# MotherForSmoothie_preliminary.net
KiCad netlist of a schematic drawn in EAGLE
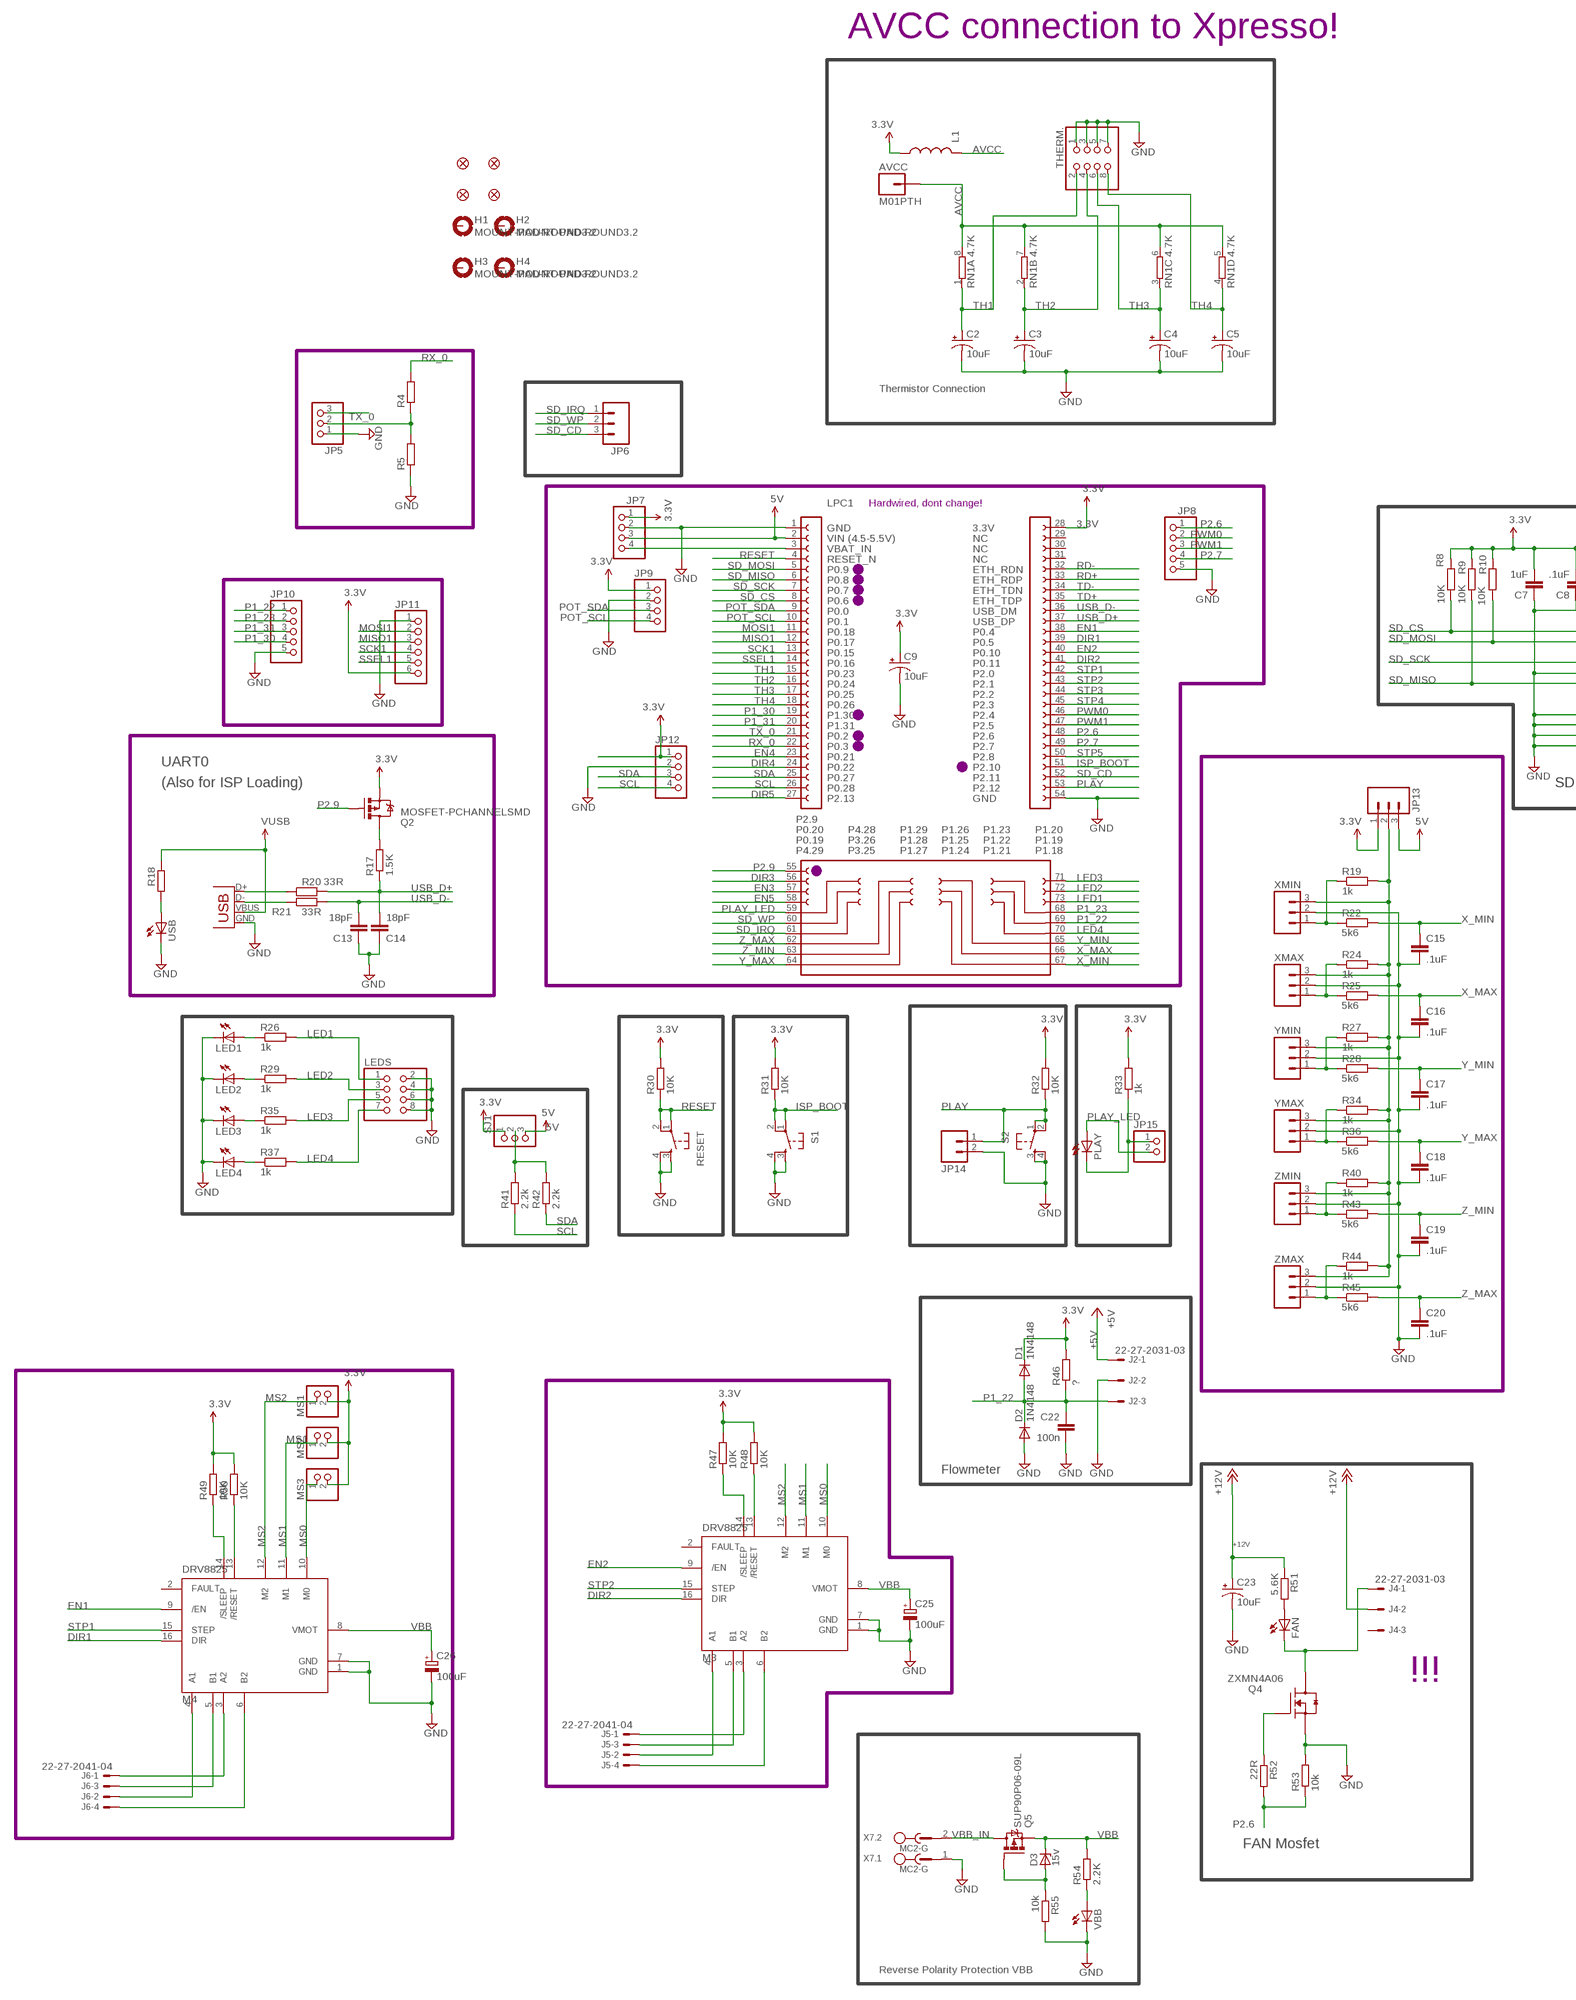
[diagram p0: schematic, sheet 1, part 1 of 2]
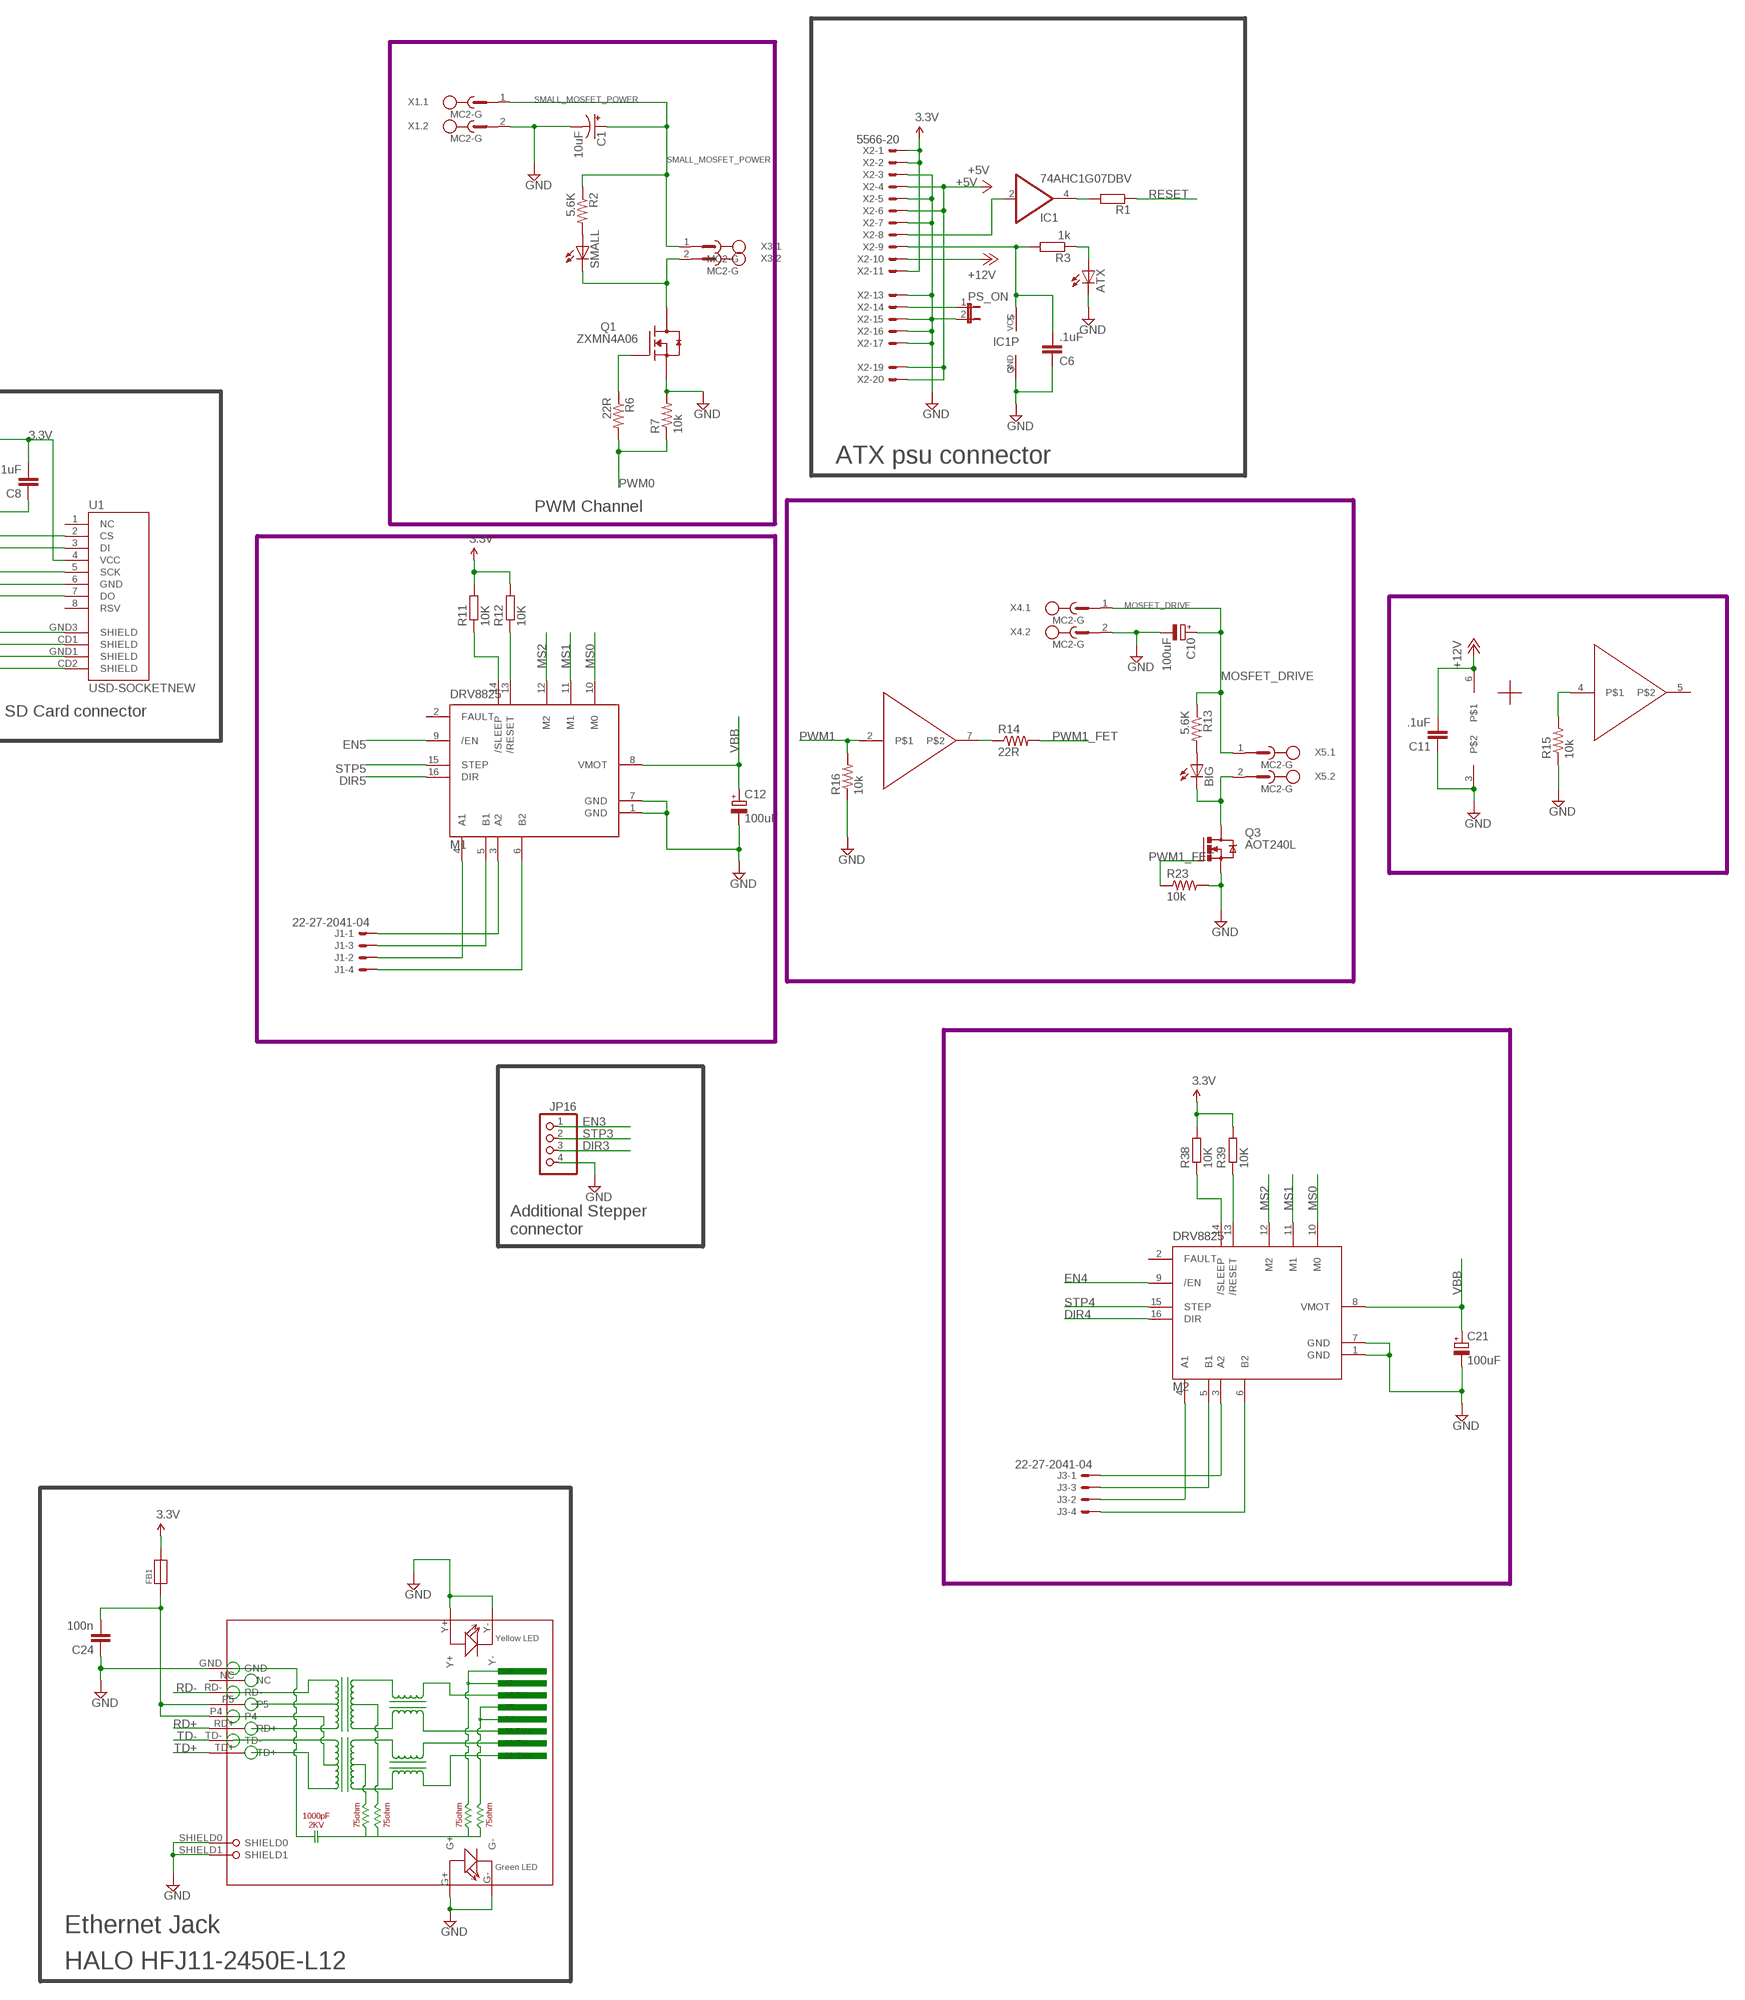
[diagram p1: schematic, sheet 1, part 2 of 2]

(export (version "E")
  (design (tool "Eeschema 10.0.6"))
  (components
    (comp (ref "ATX")
      (value "LEDCHIPLED_0805")
      (footprint "eagle-import:CHIPLED_0805")
      (libsource (lib "eagle-import") (part "LEDCHIPLED_0805"))
    )
    (comp (ref "AVCC")
      (value "M01PTH")
      (footprint "eagle-import:1X01")
      (libsource (lib "eagle-import") (part "M01PTH"))
    )
    (comp (ref "BIG")
      (value "LEDCHIP-LED0805")
      (footprint "eagle-import:CHIP-LED0805")
      (libsource (lib "eagle-import") (part "LEDCHIP-LED0805"))
    )
    (comp (ref "C1")
      (value "10uF")
      (footprint "eagle-import:EIA3216")
      (libsource (lib "eagle-import") (part "CAP_POL1206"))
    )
    (comp (ref "C2")
      (value "10uF")
      (footprint "eagle-import:EIA3216")
      (libsource (lib "eagle-import") (part "CAP_POL1206"))
    )
    (comp (ref "C3")
      (value "10uF")
      (footprint "eagle-import:EIA3216")
      (libsource (lib "eagle-import") (part "CAP_POL1206"))
    )
    (comp (ref "C4")
      (value "10uF")
      (footprint "eagle-import:EIA3216")
      (libsource (lib "eagle-import") (part "CAP_POL1206"))
    )
    (comp (ref "C5")
      (value "10uF")
      (footprint "eagle-import:EIA3216")
      (libsource (lib "eagle-import") (part "CAP_POL1206"))
    )
    (comp (ref "C6")
      (value ".1uF")
      (footprint "eagle-import:C0603")
      (libsource (lib "eagle-import") (part "C-EUC0603"))
    )
    (comp (ref "C7")
      (value "1uF")
      (footprint "eagle-import:C0603")
      (libsource (lib "eagle-import") (part "C-EUC0603"))
    )
    (comp (ref "C8")
      (value ".1uF")
      (footprint "eagle-import:C0603")
      (libsource (lib "eagle-import") (part "C-EUC0603"))
    )
    (comp (ref "C9")
      (value "10uF")
      (footprint "eagle-import:EIA3216")
      (libsource (lib "eagle-import") (part "CAP_POL1206"))
    )
    (comp (ref "C10")
      (value "100uF")
      (footprint "eagle-import:E5-8,5")
      (libsource (lib "eagle-import") (part "CPOL-EUE5-8.5"))
    )
    (comp (ref "C11")
      (value ".1uF")
      (footprint "eagle-import:C0603")
      (libsource (lib "eagle-import") (part "C-EUC0603"))
    )
    (comp (ref "C12")
      (value "100uF")
      (footprint "eagle-import:E5-8,5")
      (libsource (lib "eagle-import") (part "CPOL-EUE5-8.5"))
    )
    (comp (ref "C13")
      (value "18pF")
      (footprint "eagle-import:C0603")
      (libsource (lib "eagle-import") (part "C-EUC0603"))
    )
    (comp (ref "C14")
      (value "18pF")
      (footprint "eagle-import:C0603")
      (libsource (lib "eagle-import") (part "C-EUC0603"))
    )
    (comp (ref "C15")
      (value ".1uF")
      (footprint "eagle-import:C0603")
      (libsource (lib "eagle-import") (part "C-EUC0603"))
    )
    (comp (ref "C16")
      (value ".1uF")
      (footprint "eagle-import:C0603")
      (libsource (lib "eagle-import") (part "C-EUC0603"))
    )
    (comp (ref "C17")
      (value ".1uF")
      (footprint "eagle-import:C0603")
      (libsource (lib "eagle-import") (part "C-EUC0603"))
    )
    (comp (ref "C18")
      (value ".1uF")
      (footprint "eagle-import:C0603")
      (libsource (lib "eagle-import") (part "C-EUC0603"))
    )
    (comp (ref "C19")
      (value ".1uF")
      (footprint "eagle-import:C0603")
      (libsource (lib "eagle-import") (part "C-EUC0603"))
    )
    (comp (ref "C20")
      (value ".1uF")
      (footprint "eagle-import:C0603")
      (libsource (lib "eagle-import") (part "C-EUC0603"))
    )
    (comp (ref "C21")
      (value "100uF")
      (footprint "eagle-import:E5-8,5")
      (libsource (lib "eagle-import") (part "CPOL-EUE5-8.5"))
    )
    (comp (ref "C22")
      (value "100n")
      (footprint "eagle-import:C0603")
      (libsource (lib "eagle-import") (part "C-EUC0603"))
    )
    (comp (ref "C23")
      (value "10uF")
      (footprint "eagle-import:EIA3216")
      (libsource (lib "eagle-import") (part "CAP_POL1206"))
    )
    (comp (ref "C24")
      (value "100n")
      (footprint "eagle-import:C0603")
      (libsource (lib "eagle-import") (part "C-EUC0603"))
    )
    (comp (ref "C25")
      (value "100uF")
      (footprint "eagle-import:E5-8,5")
      (libsource (lib "eagle-import") (part "CPOL-EUE5-8.5"))
    )
    (comp (ref "C26")
      (value "100uF")
      (footprint "eagle-import:E5-8,5")
      (libsource (lib "eagle-import") (part "CPOL-EUE5-8.5"))
    )
    (comp (ref "D1")
      (value "1N4148")
      (footprint "eagle-import:MINIMELF")
      (libsource (lib "eagle-import") (part "DIODE-MINIMELF"))
    )
    (comp (ref "D2")
      (value "1N4148")
      (footprint "eagle-import:MINIMELF")
      (libsource (lib "eagle-import") (part "DIODE-MINIMELF"))
    )
    (comp (ref "D3")
      (value "15v")
      (footprint "eagle-import:SMB")
      (libsource (lib "eagle-import") (part "ZENER-DIODESMB"))
    )
    (comp (ref "FAN")
      (value "LEDCHIPLED_0805")
      (footprint "eagle-import:CHIPLED_0805")
      (libsource (lib "eagle-import") (part "LEDCHIPLED_0805"))
    )
    (comp (ref "FB1")
      (value "FERRITE")
      (footprint "eagle-import:0603")
      (libsource (lib "eagle-import") (part "FERRITE"))
    )
    (comp (ref "H1")
      (value "MOUNT-PAD-ROUND3.2")
      (footprint "eagle-import:3,2-PAD")
      (libsource (lib "eagle-import") (part "MOUNT-PAD-ROUND3.2"))
    )
    (comp (ref "H2")
      (value "MOUNT-PAD-ROUND3.2")
      (footprint "eagle-import:3,2-PAD")
      (libsource (lib "eagle-import") (part "MOUNT-PAD-ROUND3.2"))
    )
    (comp (ref "H3")
      (value "MOUNT-PAD-ROUND3.2")
      (footprint "eagle-import:3,2-PAD")
      (libsource (lib "eagle-import") (part "MOUNT-PAD-ROUND3.2"))
    )
    (comp (ref "H4")
      (value "MOUNT-PAD-ROUND3.2")
      (footprint "eagle-import:3,2-PAD")
      (libsource (lib "eagle-import") (part "MOUNT-PAD-ROUND3.2"))
    )
    (comp (ref "IC1")
      (value "74AHC1G07DBV")
      (footprint "eagle-import:SOT23-5")
      (libsource (lib "eagle-import") (part "741G07DBVAHC"))
    )
    (comp (ref "IC2")
      (value "TC4427")
      (footprint "eagle-import:SOIC8")
      (libsource (lib "eagle-import") (part "TC4427"))
    )
    (comp (ref "J1")
      (value "22-27-2041-04")
      (footprint "eagle-import:6410-04")
      (libsource (lib "eagle-import") (part "22-?-0427-2041"))
    )
    (comp (ref "J2")
      (value "22-27-2031-03")
      (footprint "eagle-import:6410-03")
      (libsource (lib "eagle-import") (part "22-?-0327-2031"))
    )
    (comp (ref "J3")
      (value "22-27-2041-04")
      (footprint "eagle-import:6410-04")
      (libsource (lib "eagle-import") (part "22-?-0427-2041"))
    )
    (comp (ref "J4")
      (value "22-27-2031-03")
      (footprint "eagle-import:6410-03")
      (libsource (lib "eagle-import") (part "22-?-0327-2031"))
    )
    (comp (ref "J5")
      (value "22-27-2041-04")
      (footprint "eagle-import:6410-04")
      (libsource (lib "eagle-import") (part "22-?-0427-2041"))
    )
    (comp (ref "J6")
      (value "22-27-2041-04")
      (footprint "eagle-import:6410-04")
      (libsource (lib "eagle-import") (part "22-?-0427-2041"))
    )
    (comp (ref "JP1")
      (value "FIDUCIAL1X2")
      (footprint "eagle-import:FIDUCIAL-1X2")
      (libsource (lib "eagle-import") (part "FIDUCIAL1X2"))
    )
    (comp (ref "JP2")
      (value "FIDUCIAL1X2")
      (footprint "eagle-import:FIDUCIAL-1X2")
      (libsource (lib "eagle-import") (part "FIDUCIAL1X2"))
    )
    (comp (ref "JP3")
      (value "FIDUCIAL1X2")
      (footprint "eagle-import:FIDUCIAL-1X2")
      (libsource (lib "eagle-import") (part "FIDUCIAL1X2"))
    )
    (comp (ref "JP4")
      (value "FIDUCIAL1X2")
      (footprint "eagle-import:FIDUCIAL-1X2")
      (libsource (lib "eagle-import") (part "FIDUCIAL1X2"))
    )
    (comp (ref "JP5")
      (value "PINHD-1X3_2.54-SMD")
      (footprint "eagle-import:1X03SMD")
      (libsource (lib "eagle-import") (part "PINHD-1X3_2.54-SMD"))
    )
    (comp (ref "JP6")
      (value "M031X03_NO_SILK")
      (footprint "eagle-import:1X03_NO_SILK")
      (libsource (lib "eagle-import") (part "M031X03_NO_SILK"))
    )
    (comp (ref "JP7")
      (value "PINHD-1X4_2.54-SMD")
      (footprint "eagle-import:1X04SMD")
      (libsource (lib "eagle-import") (part "PINHD-1X4_2.54-SMD"))
    )
    (comp (ref "JP8")
      (value "PINHD-1X5_2.54-SMD")
      (footprint "eagle-import:1X05SMD")
      (libsource (lib "eagle-import") (part "PINHD-1X5_2.54-SMD"))
    )
    (comp (ref "JP9")
      (value "PINHD-1X4_2.54-SMD")
      (footprint "eagle-import:1X04SMD")
      (libsource (lib "eagle-import") (part "PINHD-1X4_2.54-SMD"))
    )
    (comp (ref "JP10")
      (value "PINHD-1X5_2.54-SMD")
      (footprint "eagle-import:1X05SMD")
      (libsource (lib "eagle-import") (part "PINHD-1X5_2.54-SMD"))
    )
    (comp (ref "JP11")
      (value "PINHD-1X6_2.54-SMD")
      (footprint "eagle-import:1X06SMD")
      (libsource (lib "eagle-import") (part "PINHD-1X6_2.54-SMD"))
    )
    (comp (ref "JP12")
      (value "PINHD-1X4_2.54-SMD")
      (footprint "eagle-import:1X04SMD")
      (libsource (lib "eagle-import") (part "PINHD-1X4_2.54-SMD"))
    )
    (comp (ref "JP13")
      (value "M031X03_NO_SILK")
      (footprint "eagle-import:1X03_NO_SILK")
      (libsource (lib "eagle-import") (part "M031X03_NO_SILK"))
    )
    (comp (ref "JP14")
      (value "M02PTH")
      (footprint "eagle-import:1X02")
      (libsource (lib "eagle-import") (part "M02PTH"))
    )
    (comp (ref "JP15")
      (value "PINHD-1X2_2.54-SMD")
      (footprint "eagle-import:1X02SMD")
      (libsource (lib "eagle-import") (part "PINHD-1X2_2.54-SMD"))
    )
    (comp (ref "JP16")
      (value "PINHD-1X4_2.54-SMD")
      (footprint "eagle-import:1X04SMD")
      (libsource (lib "eagle-import") (part "PINHD-1X4_2.54-SMD"))
    )
    (comp (ref "L1")
      (value "INDUCTOR0603")
      (footprint "eagle-import:0603")
      (libsource (lib "eagle-import") (part "INDUCTOR0603"))
    )
    (comp (ref "LED1")
      (value "LEDCHIP-LED0805")
      (footprint "eagle-import:CHIP-LED0805")
      (libsource (lib "eagle-import") (part "LEDCHIP-LED0805"))
    )
    (comp (ref "LED2")
      (value "LEDCHIP-LED0805")
      (footprint "eagle-import:CHIP-LED0805")
      (libsource (lib "eagle-import") (part "LEDCHIP-LED0805"))
    )
    (comp (ref "LED3")
      (value "LEDCHIP-LED0805")
      (footprint "eagle-import:CHIP-LED0805")
      (libsource (lib "eagle-import") (part "LEDCHIP-LED0805"))
    )
    (comp (ref "LED4")
      (value "LEDCHIP-LED0805")
      (footprint "eagle-import:CHIP-LED0805")
      (libsource (lib "eagle-import") (part "LEDCHIP-LED0805"))
    )
    (comp (ref "LEDS")
      (value "PINHD-2X4_2.54-SMD")
      (footprint "eagle-import:2X04SMD")
      (libsource (lib "eagle-import") (part "PINHD-2X4_2.54-SMD"))
    )
    (comp (ref "LPC1")
      (value "LPCXPRESSO_LPC1769SMD_PART")
      (footprint "eagle-import:LPCXPRESSO_LPC1769_SMD")
      (libsource (lib "eagle-import") (part "LPCXPRESSO_LPC1769SMD_PART"))
    )
    (comp (ref "M1")
      (value "DRV8825")
      (footprint "eagle-import:DRV8825")
      (libsource (lib "eagle-import") (part "DRV8825"))
    )
    (comp (ref "M2")
      (value "DRV8825")
      (footprint "eagle-import:DRV8825")
      (libsource (lib "eagle-import") (part "DRV8825"))
    )
    (comp (ref "M3")
      (value "DRV8825")
      (footprint "eagle-import:DRV8825")
      (libsource (lib "eagle-import") (part "DRV8825"))
    )
    (comp (ref "M4")
      (value "DRV8825")
      (footprint "eagle-import:DRV8825")
      (libsource (lib "eagle-import") (part "DRV8825"))
    )
    (comp (ref "MS1")
      (value "PINHD-1X2_2.54-SMD")
      (footprint "eagle-import:1X02SMD")
      (libsource (lib "eagle-import") (part "PINHD-1X2_2.54-SMD"))
    )
    (comp (ref "MS2")
      (value "PINHD-1X2_2.54-SMD")
      (footprint "eagle-import:1X02SMD")
      (libsource (lib "eagle-import") (part "PINHD-1X2_2.54-SMD"))
    )
    (comp (ref "MS3")
      (value "PINHD-1X2_2.54-SMD")
      (footprint "eagle-import:1X02SMD")
      (libsource (lib "eagle-import") (part "PINHD-1X2_2.54-SMD"))
    )
    (comp (ref "PLAY")
      (value "LEDCHIPLED_0805")
      (footprint "eagle-import:CHIPLED_0805")
      (libsource (lib "eagle-import") (part "LEDCHIPLED_0805"))
    )
    (comp (ref "PS_ON")
      (value "JP1E")
      (footprint "eagle-import:JP1")
      (libsource (lib "eagle-import") (part "JP1E"))
    )
    (comp (ref "Q1")
      (value "ZXMN4A06")
      (footprint "eagle-import:SOT230P700X160-4N")
      (libsource (lib "eagle-import") (part "MOSFET-NCH_SOT-223"))
    )
    (comp (ref "Q2")
      (value "MOSFET-PCHANNELSMD")
      (footprint "eagle-import:SOT23-3")
      (libsource (lib "eagle-import") (part "MOSFET-PCHANNELSMD"))
    )
    (comp (ref "Q3")
      (value "AOT240L")
      (footprint "eagle-import:TO220BV")
      (libsource (lib "eagle-import") (part "IRF540"))
    )
    (comp (ref "Q4")
      (value "ZXMN4A06")
      (footprint "eagle-import:SOT230P700X160-4N")
      (libsource (lib "eagle-import") (part "MOSFET-NCH_SOT-223"))
    )
    (comp (ref "Q5")
      (value "SUP90P06-09L")
      (footprint "eagle-import:TO220BV")
      (libsource (lib "eagle-import") (part "IRF9530"))
    )
    (comp (ref "R1")
      (value "R-EU_R0603")
      (footprint "eagle-import:R0603")
      (libsource (lib "eagle-import") (part "R-EU_R0603"))
    )
    (comp (ref "R2")
      (value "5.6K")
      (footprint "eagle-import:R0603")
      (libsource (lib "eagle-import") (part "R-US_R0603"))
    )
    (comp (ref "R3")
      (value "1k")
      (footprint "eagle-import:R0603")
      (libsource (lib "eagle-import") (part "R-EU_R0603"))
    )
    (comp (ref "R4")
      (value "R-EU_R0603")
      (footprint "eagle-import:R0603")
      (libsource (lib "eagle-import") (part "R-EU_R0603"))
    )
    (comp (ref "R5")
      (value "R-EU_R0603")
      (footprint "eagle-import:R0603")
      (libsource (lib "eagle-import") (part "R-EU_R0603"))
    )
    (comp (ref "R6")
      (value "22R")
      (footprint "eagle-import:R0603")
      (libsource (lib "eagle-import") (part "R-US_R0603"))
    )
    (comp (ref "R7")
      (value "10k")
      (footprint "eagle-import:R0603")
      (libsource (lib "eagle-import") (part "R-US_R0603"))
    )
    (comp (ref "R8")
      (value "10K")
      (footprint "eagle-import:R0603")
      (libsource (lib "eagle-import") (part "R-EU_R0603"))
    )
    (comp (ref "R9")
      (value "10K")
      (footprint "eagle-import:R0603")
      (libsource (lib "eagle-import") (part "R-EU_R0603"))
    )
    (comp (ref "R10")
      (value "10K")
      (footprint "eagle-import:R0603")
      (libsource (lib "eagle-import") (part "R-EU_R0603"))
    )
    (comp (ref "R11")
      (value "10K")
      (footprint "eagle-import:R0603")
      (libsource (lib "eagle-import") (part "R-EU_R0603"))
    )
    (comp (ref "R12")
      (value "10K")
      (footprint "eagle-import:R0603")
      (libsource (lib "eagle-import") (part "R-EU_R0603"))
    )
    (comp (ref "R13")
      (value "5.6K")
      (footprint "eagle-import:R0603")
      (libsource (lib "eagle-import") (part "R-US_R0603"))
    )
    (comp (ref "R14")
      (value "22R")
      (footprint "eagle-import:R0603")
      (libsource (lib "eagle-import") (part "R-US_R0603"))
    )
    (comp (ref "R15")
      (value "10k")
      (footprint "eagle-import:R0603")
      (libsource (lib "eagle-import") (part "R-US_R0603"))
    )
    (comp (ref "R16")
      (value "10k")
      (footprint "eagle-import:R0603")
      (libsource (lib "eagle-import") (part "R-US_R0603"))
    )
    (comp (ref "R17")
      (value "1.5K")
      (footprint "eagle-import:R0603")
      (libsource (lib "eagle-import") (part "R-EU_R0603"))
    )
    (comp (ref "R18")
      (value "R-EU_R0603")
      (footprint "eagle-import:R0603")
      (libsource (lib "eagle-import") (part "R-EU_R0603"))
    )
    (comp (ref "R19")
      (value "1k")
      (footprint "eagle-import:R0603")
      (libsource (lib "eagle-import") (part "R-EU_R0603"))
    )
    (comp (ref "R20")
      (value "33R")
      (footprint "eagle-import:R0603")
      (libsource (lib "eagle-import") (part "R-EU_R0603"))
    )
    (comp (ref "R21")
      (value "33R")
      (footprint "eagle-import:R0603")
      (libsource (lib "eagle-import") (part "R-EU_R0603"))
    )
    (comp (ref "R22")
      (value "5k6")
      (footprint "eagle-import:R0603")
      (libsource (lib "eagle-import") (part "R-EU_R0603"))
    )
    (comp (ref "R23")
      (value "10k")
      (footprint "eagle-import:R0603")
      (libsource (lib "eagle-import") (part "R-US_R0603"))
    )
    (comp (ref "R24")
      (value "1k")
      (footprint "eagle-import:R0603")
      (libsource (lib "eagle-import") (part "R-EU_R0603"))
    )
    (comp (ref "R25")
      (value "5k6")
      (footprint "eagle-import:R0603")
      (libsource (lib "eagle-import") (part "R-EU_R0603"))
    )
    (comp (ref "R26")
      (value "1k")
      (footprint "eagle-import:R0603")
      (libsource (lib "eagle-import") (part "R-EU_R0603"))
    )
    (comp (ref "R27")
      (value "1k")
      (footprint "eagle-import:R0603")
      (libsource (lib "eagle-import") (part "R-EU_R0603"))
    )
    (comp (ref "R28")
      (value "5k6")
      (footprint "eagle-import:R0603")
      (libsource (lib "eagle-import") (part "R-EU_R0603"))
    )
    (comp (ref "R29")
      (value "1k")
      (footprint "eagle-import:R0603")
      (libsource (lib "eagle-import") (part "R-EU_R0603"))
    )
    (comp (ref "R30")
      (value "10K")
      (footprint "eagle-import:R0603")
      (libsource (lib "eagle-import") (part "R-EU_R0603"))
    )
    (comp (ref "R31")
      (value "10K")
      (footprint "eagle-import:R0603")
      (libsource (lib "eagle-import") (part "R-EU_R0603"))
    )
    (comp (ref "R32")
      (value "10K")
      (footprint "eagle-import:R0603")
      (libsource (lib "eagle-import") (part "R-EU_R0603"))
    )
    (comp (ref "R33")
      (value "1k")
      (footprint "eagle-import:R0603")
      (libsource (lib "eagle-import") (part "R-EU_R0603"))
    )
    (comp (ref "R34")
      (value "1k")
      (footprint "eagle-import:R0603")
      (libsource (lib "eagle-import") (part "R-EU_R0603"))
    )
    (comp (ref "R35")
      (value "1k")
      (footprint "eagle-import:R0603")
      (libsource (lib "eagle-import") (part "R-EU_R0603"))
    )
    (comp (ref "R36")
      (value "5k6")
      (footprint "eagle-import:R0603")
      (libsource (lib "eagle-import") (part "R-EU_R0603"))
    )
    (comp (ref "R37")
      (value "1k")
      (footprint "eagle-import:R0603")
      (libsource (lib "eagle-import") (part "R-EU_R0603"))
    )
    (comp (ref "R38")
      (value "10K")
      (footprint "eagle-import:R0603")
      (libsource (lib "eagle-import") (part "R-EU_R0603"))
    )
    (comp (ref "R39")
      (value "10K")
      (footprint "eagle-import:R0603")
      (libsource (lib "eagle-import") (part "R-EU_R0603"))
    )
    (comp (ref "R40")
      (value "1k")
      (footprint "eagle-import:R0603")
      (libsource (lib "eagle-import") (part "R-EU_R0603"))
    )
    (comp (ref "R41")
      (value "2.2k")
      (footprint "eagle-import:R0603")
      (libsource (lib "eagle-import") (part "R-EU_R0603"))
    )
    (comp (ref "R42")
      (value "2.2k")
      (footprint "eagle-import:R0603")
      (libsource (lib "eagle-import") (part "R-EU_R0603"))
    )
    (comp (ref "R43")
      (value "5k6")
      (footprint "eagle-import:R0603")
      (libsource (lib "eagle-import") (part "R-EU_R0603"))
    )
    (comp (ref "R44")
      (value "1k")
      (footprint "eagle-import:R0603")
      (libsource (lib "eagle-import") (part "R-EU_R0603"))
    )
    (comp (ref "R45")
      (value "5k6")
      (footprint "eagle-import:R0603")
      (libsource (lib "eagle-import") (part "R-EU_R0603"))
    )
    (comp (ref "R46")
      (value "?")
      (footprint "eagle-import:R0603")
      (libsource (lib "eagle-import") (part "R-EU_R0603"))
    )
    (comp (ref "R47")
      (value "10K")
      (footprint "eagle-import:R0603")
      (libsource (lib "eagle-import") (part "R-EU_R0603"))
    )
    (comp (ref "R48")
      (value "10K")
      (footprint "eagle-import:R0603")
      (libsource (lib "eagle-import") (part "R-EU_R0603"))
    )
    (comp (ref "R49")
      (value "10K")
      (footprint "eagle-import:R0603")
      (libsource (lib "eagle-import") (part "R-EU_R0603"))
    )
    (comp (ref "R50")
      (value "10K")
      (footprint "eagle-import:R0603")
      (libsource (lib "eagle-import") (part "R-EU_R0603"))
    )
    (comp (ref "R51")
      (value "5.6K")
      (footprint "eagle-import:R0603")
      (libsource (lib "eagle-import") (part "R-EU_R0603"))
    )
    (comp (ref "R52")
      (value "22R")
      (footprint "eagle-import:R0603")
      (libsource (lib "eagle-import") (part "R-EU_R0603"))
    )
    (comp (ref "R53")
      (value "10k")
      (footprint "eagle-import:R0603")
      (libsource (lib "eagle-import") (part "R-EU_R0603"))
    )
    (comp (ref "R54")
      (value "2.2K")
      (footprint "eagle-import:R0603")
      (libsource (lib "eagle-import") (part "R-EU_R0603"))
    )
    (comp (ref "R55")
      (value "10k")
      (footprint "eagle-import:R0603")
      (libsource (lib "eagle-import") (part "R-EU_R0603"))
    )
    (comp (ref "RESET")
      (value "TAC_SWITCHSMD")
      (footprint "eagle-import:TACTILE_SWITCH_SMD")
      (libsource (lib "eagle-import") (part "TAC_SWITCHSMD"))
    )
    (comp (ref "RJ1")
      (value "HR911105A")
      (footprint "eagle-import:HR911105A")
      (libsource (lib "eagle-import") (part "HR911105A"))
    )
    (comp (ref "RN1")
      (value "4.7K")
      (footprint "eagle-import:0603-ARV")
      (libsource (lib "eagle-import") (part "4R-N0603-ARV"))
    )
    (comp (ref "S1")
      (value "TAC_SWITCHSMD")
      (footprint "eagle-import:TACTILE_SWITCH_SMD")
      (libsource (lib "eagle-import") (part "TAC_SWITCHSMD"))
    )
    (comp (ref "S2")
      (value "TAC_SWITCHSMD")
      (footprint "eagle-import:TACTILE_SWITCH_SMD")
      (libsource (lib "eagle-import") (part "TAC_SWITCHSMD"))
    )
    (comp (ref "SJ1")
      (value "PINHD-1X3_2.54-SMD")
      (footprint "eagle-import:1X03SMD")
      (libsource (lib "eagle-import") (part "PINHD-1X3_2.54-SMD"))
    )
    (comp (ref "SMALL")
      (value "LEDCHIP-LED0805")
      (footprint "eagle-import:CHIP-LED0805")
      (libsource (lib "eagle-import") (part "LEDCHIP-LED0805"))
    )
    (comp (ref "THERM.")
      (value "PINHD-2X4MICROMATCH-SMD")
      (footprint "eagle-import:SMDTOP8")
      (libsource (lib "eagle-import") (part "PINHD-2X4MICROMATCH-SMD"))
    )
    (comp (ref "U1")
      (value "USD-SOCKETNEW")
      (footprint "eagle-import:MICRO-SD-SOCKET-PP")
      (libsource (lib "eagle-import") (part "USD-SOCKETNEW"))
    )
    (comp (ref "USB")
      (value "LEDCHIPLED_0805")
      (footprint "eagle-import:CHIPLED_0805")
      (libsource (lib "eagle-import") (part "LEDCHIPLED_0805"))
    )
    (comp (ref "VBB")
      (value "LEDCHIPLED_0805")
      (footprint "eagle-import:CHIPLED_0805")
      (libsource (lib "eagle-import") (part "LEDCHIPLED_0805"))
    )
    (comp (ref "X1")
      (value "MC2-G")
      (footprint "eagle-import:MC2-G")
      (libsource (lib "eagle-import") (part "MC2-G"))
    )
    (comp (ref "X2")
      (value "5566-20")
      (footprint "eagle-import:5566-20")
      (libsource (lib "eagle-import") (part "5566-20"))
    )
    (comp (ref "X3")
      (value "MC2-G")
      (footprint "eagle-import:MC2-G")
      (libsource (lib "eagle-import") (part "MC2-G"))
    )
    (comp (ref "X4")
      (value "MC2-G")
      (footprint "eagle-import:MC2-G")
      (libsource (lib "eagle-import") (part "MC2-G"))
    )
    (comp (ref "X5")
      (value "MC2-G")
      (footprint "eagle-import:MC2-G")
      (libsource (lib "eagle-import") (part "MC2-G"))
    )
    (comp (ref "X6")
      (value "USB-MICROB")
      (footprint "eagle-import:USB-MICROB")
      (libsource (lib "eagle-import") (part "USB-MICROB"))
    )
    (comp (ref "X7")
      (value "MC2-G")
      (footprint "eagle-import:MC2-G")
      (libsource (lib "eagle-import") (part "MC2-G"))
    )
    (comp (ref "XMAX")
      (value "M031X03_NO_SILK")
      (footprint "eagle-import:1X03_NO_SILK")
      (libsource (lib "eagle-import") (part "M031X03_NO_SILK"))
    )
    (comp (ref "XMIN")
      (value "M031X03_NO_SILK")
      (footprint "eagle-import:1X03_NO_SILK")
      (libsource (lib "eagle-import") (part "M031X03_NO_SILK"))
    )
    (comp (ref "YMAX")
      (value "M031X03_NO_SILK")
      (footprint "eagle-import:1X03_NO_SILK")
      (libsource (lib "eagle-import") (part "M031X03_NO_SILK"))
    )
    (comp (ref "YMIN")
      (value "M031X03_NO_SILK")
      (footprint "eagle-import:1X03_NO_SILK")
      (libsource (lib "eagle-import") (part "M031X03_NO_SILK"))
    )
    (comp (ref "ZMAX")
      (value "M031X03_NO_SILK")
      (footprint "eagle-import:1X03_NO_SILK")
      (libsource (lib "eagle-import") (part "M031X03_NO_SILK"))
    )
    (comp (ref "ZMIN")
      (value "M031X03_NO_SILK")
      (footprint "eagle-import:1X03_NO_SILK")
      (libsource (lib "eagle-import") (part "M031X03_NO_SILK"))
    )
  )
  (nets
    (net (code "1") (name "+5V") (class "Default")
      (node (ref "J2") (pin "1") (pinfunction "S_1") (pintype "passive"))
      (node (ref "X2") (pin "19") (pinfunction "S_19") (pintype "passive"))
      (node (ref "X2") (pin "20") (pinfunction "S_20") (pintype "passive"))
      (node (ref "X2") (pin "4") (pinfunction "S_4") (pintype "passive"))
      (node (ref "X2") (pin "6") (pinfunction "S_6") (pintype "passive"))
    )
    (net (code "2") (name "+12V") (class "Default")
      (node (ref "C11") (pin "2") (pinfunction "2_2") (pintype "passive"))
      (node (ref "C23") (pin "A") (pinfunction "+_A") (pintype "passive"))
      (node (ref "IC2") (pin "6") (pinfunction "P$1_6") (pintype "bidirectional"))
      (node (ref "J4") (pin "2") (pinfunction "S_2") (pintype "passive"))
      (node (ref "R51") (pin "1") (pinfunction "1_1") (pintype "passive"))
      (node (ref "X2") (pin "10") (pinfunction "S_10") (pintype "passive"))
    )
    (net (code "3") (name "/AVCC") (class "Default")
      (node (ref "AVCC") (pin "1") (pinfunction "1_1") (pintype "passive"))
      (node (ref "L1") (pin "1") (pinfunction "1_1") (pintype "passive"))
      (node (ref "RN1") (pin "5") (pinfunction "2_5") (pintype "passive"))
      (node (ref "RN1") (pin "6") (pinfunction "2_6") (pintype "passive"))
      (node (ref "RN1") (pin "7") (pinfunction "2_7") (pintype "passive"))
      (node (ref "RN1") (pin "8") (pinfunction "2_8") (pintype "passive"))
    )
    (net (code "4") (name "/DIR1") (class "Default")
      (node (ref "LPC1") (pin "39") (pinfunction "39_39") (pintype "passive"))
      (node (ref "M4") (pin "16") (pinfunction "DIR_16") (pintype "input"))
    )
    (net (code "5") (name "/DIR2") (class "Default")
      (node (ref "LPC1") (pin "41") (pinfunction "41_41") (pintype "passive"))
      (node (ref "M3") (pin "16") (pinfunction "DIR_16") (pintype "input"))
    )
    (net (code "6") (name "/DIR3") (class "Default")
      (node (ref "JP16") (pin "3") (pinfunction "3_3") (pintype "passive"))
      (node (ref "LPC1") (pin "56") (pinfunction "56_56") (pintype "passive"))
    )
    (net (code "7") (name "/DIR4") (class "Default")
      (node (ref "LPC1") (pin "24") (pinfunction "24_24") (pintype "passive"))
      (node (ref "M2") (pin "16") (pinfunction "DIR_16") (pintype "input"))
    )
    (net (code "8") (name "/DIR5") (class "Default")
      (node (ref "LPC1") (pin "27") (pinfunction "27_27") (pintype "passive"))
      (node (ref "M1") (pin "16") (pinfunction "DIR_16") (pintype "input"))
    )
    (net (code "9") (name "/EN1") (class "Default")
      (node (ref "LPC1") (pin "38") (pinfunction "38_38") (pintype "passive"))
      (node (ref "M4") (pin "9") (pinfunction "/EN_9") (pintype "input"))
    )
    (net (code "10") (name "/EN2") (class "Default")
      (node (ref "LPC1") (pin "40") (pinfunction "40_40") (pintype "passive"))
      (node (ref "M3") (pin "9") (pinfunction "/EN_9") (pintype "input"))
    )
    (net (code "11") (name "/EN3") (class "Default")
      (node (ref "JP16") (pin "1") (pinfunction "1_1") (pintype "passive"))
      (node (ref "LPC1") (pin "57") (pinfunction "57_57") (pintype "passive"))
    )
    (net (code "12") (name "/EN4") (class "Default")
      (node (ref "LPC1") (pin "23") (pinfunction "23_23") (pintype "passive"))
      (node (ref "M2") (pin "9") (pinfunction "/EN_9") (pintype "input"))
    )
    (net (code "13") (name "/EN5") (class "Default")
      (node (ref "LPC1") (pin "58") (pinfunction "58_58") (pintype "passive"))
      (node (ref "M1") (pin "9") (pinfunction "/EN_9") (pintype "input"))
    )
    (net (code "14") (name "/ISP_BOOT") (class "Default")
      (node (ref "LPC1") (pin "51") (pinfunction "51_51") (pintype "passive"))
      (node (ref "R31") (pin "1") (pinfunction "1_1") (pintype "passive"))
      (node (ref "S1") (pin "1") (pinfunction "1_1") (pintype "passive"))
      (node (ref "S1") (pin "2") (pinfunction "2_2") (pintype "passive"))
    )
    (net (code "15") (name "/LED1") (class "Default")
      (node (ref "LEDS") (pin "1") (pinfunction "1_1") (pintype "passive"))
      (node (ref "LPC1") (pin "73") (pinfunction "73_73") (pintype "passive"))
      (node (ref "R26") (pin "2") (pinfunction "2_2") (pintype "passive"))
    )
    (net (code "16") (name "/LED2") (class "Default")
      (node (ref "LEDS") (pin "3") (pinfunction "3_3") (pintype "passive"))
      (node (ref "LPC1") (pin "72") (pinfunction "72_72") (pintype "passive"))
      (node (ref "R29") (pin "2") (pinfunction "2_2") (pintype "passive"))
    )
    (net (code "17") (name "/LED3") (class "Default")
      (node (ref "LEDS") (pin "5") (pinfunction "5_5") (pintype "passive"))
      (node (ref "LPC1") (pin "71") (pinfunction "71_71") (pintype "passive"))
      (node (ref "R35") (pin "2") (pinfunction "2_2") (pintype "passive"))
    )
    (net (code "18") (name "/LED4") (class "Default")
      (node (ref "LEDS") (pin "7") (pinfunction "7_7") (pintype "passive"))
      (node (ref "LPC1") (pin "70") (pinfunction "70_70") (pintype "passive"))
      (node (ref "R37") (pin "2") (pinfunction "2_2") (pintype "passive"))
    )
    (net (code "19") (name "/MISO1") (class "Default")
      (node (ref "JP11") (pin "3") (pinfunction "3_3") (pintype "passive"))
      (node (ref "LPC1") (pin "12") (pinfunction "12_12") (pintype "passive"))
    )
    (net (code "20") (name "/MOSFET_DRIVE") (class "Default")
      (node (ref "C10") (pin "+") (pinfunction "+_+") (pintype "passive"))
      (node (ref "R13") (pin "1") (pinfunction "1_1") (pintype "passive"))
      (node (ref "X4") (pin "1") (pinfunction "SK_1") (pintype "passive"))
      (node (ref "X5") (pin "1") (pinfunction "SK_1") (pintype "passive"))
    )
    (net (code "21") (name "/MOSI1") (class "Default")
      (node (ref "JP11") (pin "2") (pinfunction "2_2") (pintype "passive"))
      (node (ref "LPC1") (pin "11") (pinfunction "11_11") (pintype "passive"))
    )
    (net (code "22") (name "/MS0") (class "Default")
      (node (ref "M1") (pin "10") (pinfunction "M0_10") (pintype "input"))
      (node (ref "M2") (pin "10") (pinfunction "M0_10") (pintype "input"))
      (node (ref "M3") (pin "10") (pinfunction "M0_10") (pintype "input"))
      (node (ref "M4") (pin "10") (pinfunction "M0_10") (pintype "input"))
      (node (ref "MS3") (pin "1") (pinfunction "1_1") (pintype "passive"))
    )
    (net (code "23") (name "/MS1") (class "Default")
      (node (ref "M1") (pin "11") (pinfunction "M1_11") (pintype "input"))
      (node (ref "M2") (pin "11") (pinfunction "M1_11") (pintype "input"))
      (node (ref "M3") (pin "11") (pinfunction "M1_11") (pintype "input"))
      (node (ref "M4") (pin "11") (pinfunction "M1_11") (pintype "input"))
      (node (ref "MS2") (pin "1") (pinfunction "1_1") (pintype "passive"))
    )
    (net (code "24") (name "/MS2") (class "Default")
      (node (ref "M1") (pin "12") (pinfunction "M2_12") (pintype "input"))
      (node (ref "M2") (pin "12") (pinfunction "M2_12") (pintype "input"))
      (node (ref "M3") (pin "12") (pinfunction "M2_12") (pintype "input"))
      (node (ref "M4") (pin "12") (pinfunction "M2_12") (pintype "input"))
      (node (ref "MS1") (pin "1") (pinfunction "1_1") (pintype "passive"))
    )
    (net (code "25") (name "/P1_22") (class "Default")
      (node (ref "C22") (pin "1") (pinfunction "1_1") (pintype "passive"))
      (node (ref "D1") (pin "A") (pinfunction "A_A") (pintype "passive"))
      (node (ref "D2") (pin "C") (pinfunction "C_C") (pintype "passive"))
      (node (ref "J2") (pin "3") (pinfunction "S_3") (pintype "passive"))
      (node (ref "JP10") (pin "1") (pinfunction "1_1") (pintype "passive"))
      (node (ref "LPC1") (pin "69") (pinfunction "69_69") (pintype "passive"))
      (node (ref "R46") (pin "1") (pinfunction "1_1") (pintype "passive"))
    )
    (net (code "26") (name "/P1_23") (class "Default")
      (node (ref "JP10") (pin "2") (pinfunction "2_2") (pintype "passive"))
      (node (ref "LPC1") (pin "68") (pinfunction "68_68") (pintype "passive"))
    )
    (net (code "27") (name "/P1_30") (class "Default")
      (node (ref "JP10") (pin "4") (pinfunction "4_4") (pintype "passive"))
      (node (ref "LPC1") (pin "19") (pinfunction "19_19") (pintype "passive"))
    )
    (net (code "28") (name "/P1_31") (class "Default")
      (node (ref "JP10") (pin "3") (pinfunction "3_3") (pintype "passive"))
      (node (ref "LPC1") (pin "20") (pinfunction "20_20") (pintype "passive"))
    )
    (net (code "29") (name "/P2.6") (class "Default")
      (node (ref "JP8") (pin "1") (pinfunction "1_1") (pintype "passive"))
      (node (ref "LPC1") (pin "48") (pinfunction "48_48") (pintype "passive"))
      (node (ref "R52") (pin "2") (pinfunction "2_2") (pintype "passive"))
      (node (ref "R53") (pin "1") (pinfunction "1_1") (pintype "passive"))
    )
    (net (code "30") (name "/P2.7") (class "Default")
      (node (ref "JP8") (pin "4") (pinfunction "4_4") (pintype "passive"))
      (node (ref "LPC1") (pin "49") (pinfunction "49_49") (pintype "passive"))
    )
    (net (code "31") (name "/P2.9") (class "Default")
      (node (ref "LPC1") (pin "55") (pinfunction "55_55") (pintype "passive"))
      (node (ref "Q2") (pin "1") (pinfunction "G_1") (pintype "passive"))
    )
    (net (code "32") (name "/PLAY") (class "Default")
      (node (ref "JP14") (pin "1") (pinfunction "1_1") (pintype "passive"))
      (node (ref "LPC1") (pin "53") (pinfunction "53_53") (pintype "passive"))
      (node (ref "R32") (pin "1") (pinfunction "1_1") (pintype "passive"))
      (node (ref "S2") (pin "1") (pinfunction "1_1") (pintype "passive"))
      (node (ref "S2") (pin "2") (pinfunction "2_2") (pintype "passive"))
    )
    (net (code "33") (name "/PLAY_LED") (class "Default")
      (node (ref "JP15") (pin "2") (pinfunction "2_2") (pintype "passive"))
      (node (ref "LPC1") (pin "59") (pinfunction "59_59") (pintype "passive"))
      (node (ref "PLAY") (pin "A") (pinfunction "A_A") (pintype "passive"))
    )
    (net (code "34") (name "/POT_SCL") (class "Default")
      (node (ref "JP9") (pin "4") (pinfunction "4_4") (pintype "passive"))
      (node (ref "LPC1") (pin "10") (pinfunction "10_10") (pintype "passive"))
    )
    (net (code "35") (name "/POT_SDA") (class "Default")
      (node (ref "JP9") (pin "3") (pinfunction "3_3") (pintype "passive"))
      (node (ref "LPC1") (pin "9") (pinfunction "9_9") (pintype "passive"))
    )
    (net (code "36") (name "/PWM0") (class "Default")
      (node (ref "JP8") (pin "2") (pinfunction "2_2") (pintype "passive"))
      (node (ref "LPC1") (pin "46") (pinfunction "46_46") (pintype "passive"))
      (node (ref "R6") (pin "2") (pinfunction "2_2") (pintype "passive"))
      (node (ref "R7") (pin "1") (pinfunction "1_1") (pintype "passive"))
    )
    (net (code "37") (name "/PWM1") (class "Default")
      (node (ref "IC2") (pin "2") (pinfunction "P$1_2") (pintype "bidirectional"))
      (node (ref "JP8") (pin "3") (pinfunction "3_3") (pintype "passive"))
      (node (ref "LPC1") (pin "47") (pinfunction "47_47") (pintype "passive"))
      (node (ref "R16") (pin "2") (pinfunction "2_2") (pintype "passive"))
    )
    (net (code "38") (name "/PWM1_FET") (class "Default")
      (node (ref "Q3") (pin "G") (pinfunction "G_G") (pintype "passive"))
      (node (ref "R14") (pin "2") (pinfunction "2_2") (pintype "passive"))
      (node (ref "R23") (pin "1") (pinfunction "1_1") (pintype "passive"))
    )
    (net (code "39") (name "/RD+") (class "Default")
      (node (ref "LPC1") (pin "33") (pinfunction "33_33") (pintype "passive"))
      (node (ref "RJ1") (pin "RD+") (pinfunction "RD+_RD+") (pintype "bidirectional"))
    )
    (net (code "40") (name "/RD-") (class "Default")
      (node (ref "LPC1") (pin "32") (pinfunction "32_32") (pintype "passive"))
      (node (ref "RJ1") (pin "RD-") (pinfunction "RD-_RD-") (pintype "bidirectional"))
    )
    (net (code "41") (name "/RESET") (class "Default")
      (node (ref "LPC1") (pin "4") (pinfunction "4_4") (pintype "passive"))
      (node (ref "R1") (pin "1") (pinfunction "1_1") (pintype "passive"))
      (node (ref "R30") (pin "1") (pinfunction "1_1") (pintype "passive"))
      (node (ref "RESET") (pin "1") (pinfunction "1_1") (pintype "passive"))
      (node (ref "RESET") (pin "2") (pinfunction "2_2") (pintype "passive"))
    )
    (net (code "42") (name "/RX_0") (class "Default")
      (node (ref "LPC1") (pin "22") (pinfunction "22_22") (pintype "passive"))
      (node (ref "R4") (pin "2") (pinfunction "2_2") (pintype "passive"))
    )
    (net (code "43") (name "/SCK1") (class "Default")
      (node (ref "JP11") (pin "4") (pinfunction "4_4") (pintype "passive"))
      (node (ref "LPC1") (pin "13") (pinfunction "13_13") (pintype "passive"))
    )
    (net (code "44") (name "/SCL") (class "Default")
      (node (ref "JP12") (pin "4") (pinfunction "4_4") (pintype "passive"))
      (node (ref "LPC1") (pin "26") (pinfunction "26_26") (pintype "passive"))
      (node (ref "R41") (pin "1") (pinfunction "1_1") (pintype "passive"))
    )
    (net (code "45") (name "/SDA") (class "Default")
      (node (ref "JP12") (pin "3") (pinfunction "3_3") (pintype "passive"))
      (node (ref "LPC1") (pin "25") (pinfunction "25_25") (pintype "passive"))
      (node (ref "R42") (pin "1") (pinfunction "1_1") (pintype "passive"))
    )
    (net (code "46") (name "/SD_CD") (class "Default")
      (node (ref "JP6") (pin "3") (pinfunction "3_3") (pintype "passive"))
      (node (ref "LPC1") (pin "52") (pinfunction "52_52") (pintype "passive"))
    )
    (net (code "47") (name "/SD_CS") (class "Default")
      (node (ref "LPC1") (pin "8") (pinfunction "8_8") (pintype "passive"))
      (node (ref "R8") (pin "1") (pinfunction "1_1") (pintype "passive"))
      (node (ref "U1") (pin "2") (pinfunction "CS_2") (pintype "bidirectional"))
    )
    (net (code "48") (name "/SD_IRQ") (class "Default")
      (node (ref "JP6") (pin "1") (pinfunction "1_1") (pintype "passive"))
      (node (ref "LPC1") (pin "61") (pinfunction "61_61") (pintype "passive"))
    )
    (net (code "49") (name "/SD_MISO") (class "Default")
      (node (ref "LPC1") (pin "6") (pinfunction "6_6") (pintype "passive"))
      (node (ref "R9") (pin "1") (pinfunction "1_1") (pintype "passive"))
      (node (ref "U1") (pin "7") (pinfunction "DO_7") (pintype "bidirectional"))
    )
    (net (code "50") (name "/SD_MOSI") (class "Default")
      (node (ref "LPC1") (pin "5") (pinfunction "5_5") (pintype "passive"))
      (node (ref "R10") (pin "1") (pinfunction "1_1") (pintype "passive"))
      (node (ref "U1") (pin "3") (pinfunction "DI_3") (pintype "bidirectional"))
    )
    (net (code "51") (name "/SD_SCK") (class "Default")
      (node (ref "LPC1") (pin "7") (pinfunction "7_7") (pintype "passive"))
      (node (ref "U1") (pin "5") (pinfunction "SCK_5") (pintype "bidirectional"))
    )
    (net (code "52") (name "/SD_WP") (class "Default")
      (node (ref "JP6") (pin "2") (pinfunction "2_2") (pintype "passive"))
      (node (ref "LPC1") (pin "60") (pinfunction "60_60") (pintype "passive"))
    )
    (net (code "53") (name "/SMALL_MOSFET_POWER") (class "Default")
      (node (ref "C1") (pin "A") (pinfunction "+_A") (pintype "passive"))
      (node (ref "R2") (pin "1") (pinfunction "1_1") (pintype "passive"))
      (node (ref "X1") (pin "1") (pinfunction "SK_1") (pintype "passive"))
      (node (ref "X3") (pin "1") (pinfunction "SK_1") (pintype "passive"))
    )
    (net (code "54") (name "/SSEL1") (class "Default")
      (node (ref "JP11") (pin "5") (pinfunction "5_5") (pintype "passive"))
      (node (ref "LPC1") (pin "14") (pinfunction "14_14") (pintype "passive"))
    )
    (net (code "55") (name "/STP1") (class "Default")
      (node (ref "LPC1") (pin "42") (pinfunction "42_42") (pintype "passive"))
      (node (ref "M4") (pin "15") (pinfunction "STEP_15") (pintype "input"))
    )
    (net (code "56") (name "/STP2") (class "Default")
      (node (ref "LPC1") (pin "43") (pinfunction "43_43") (pintype "passive"))
      (node (ref "M3") (pin "15") (pinfunction "STEP_15") (pintype "input"))
    )
    (net (code "57") (name "/STP3") (class "Default")
      (node (ref "JP16") (pin "2") (pinfunction "2_2") (pintype "passive"))
      (node (ref "LPC1") (pin "44") (pinfunction "44_44") (pintype "passive"))
    )
    (net (code "58") (name "/STP4") (class "Default")
      (node (ref "LPC1") (pin "45") (pinfunction "45_45") (pintype "passive"))
      (node (ref "M2") (pin "15") (pinfunction "STEP_15") (pintype "input"))
    )
    (net (code "59") (name "/STP5") (class "Default")
      (node (ref "LPC1") (pin "50") (pinfunction "50_50") (pintype "passive"))
      (node (ref "M1") (pin "15") (pinfunction "STEP_15") (pintype "input"))
    )
    (net (code "60") (name "/TD+") (class "Default")
      (node (ref "LPC1") (pin "35") (pinfunction "35_35") (pintype "passive"))
      (node (ref "RJ1") (pin "TD+") (pinfunction "TD+_TD+") (pintype "bidirectional"))
    )
    (net (code "61") (name "/TD-") (class "Default")
      (node (ref "LPC1") (pin "34") (pinfunction "34_34") (pintype "passive"))
      (node (ref "RJ1") (pin "TD-") (pinfunction "TD-_TD-") (pintype "bidirectional"))
    )
    (net (code "62") (name "/TH1") (class "Default")
      (node (ref "C2") (pin "A") (pinfunction "+_A") (pintype "passive"))
      (node (ref "LPC1") (pin "15") (pinfunction "15_15") (pintype "passive"))
      (node (ref "RN1") (pin "1") (pinfunction "1_1") (pintype "passive"))
      (node (ref "THERM.") (pin "2") (pinfunction "2_2") (pintype "passive"))
    )
    (net (code "63") (name "/TH2") (class "Default")
      (node (ref "C3") (pin "A") (pinfunction "+_A") (pintype "passive"))
      (node (ref "LPC1") (pin "16") (pinfunction "16_16") (pintype "passive"))
      (node (ref "RN1") (pin "2") (pinfunction "1_2") (pintype "passive"))
      (node (ref "THERM.") (pin "4") (pinfunction "4_4") (pintype "passive"))
    )
    (net (code "64") (name "/TH3") (class "Default")
      (node (ref "C4") (pin "A") (pinfunction "+_A") (pintype "passive"))
      (node (ref "LPC1") (pin "17") (pinfunction "17_17") (pintype "passive"))
      (node (ref "RN1") (pin "3") (pinfunction "1_3") (pintype "passive"))
      (node (ref "THERM.") (pin "6") (pinfunction "6_6") (pintype "passive"))
    )
    (net (code "65") (name "/TH4") (class "Default")
      (node (ref "C5") (pin "A") (pinfunction "+_A") (pintype "passive"))
      (node (ref "LPC1") (pin "18") (pinfunction "18_18") (pintype "passive"))
      (node (ref "RN1") (pin "4") (pinfunction "1_4") (pintype "passive"))
      (node (ref "THERM.") (pin "8") (pinfunction "8_8") (pintype "passive"))
    )
    (net (code "66") (name "/TX_0") (class "Default")
      (node (ref "JP5") (pin "3") (pinfunction "3_3") (pintype "passive"))
      (node (ref "LPC1") (pin "21") (pinfunction "21_21") (pintype "passive"))
    )
    (net (code "67") (name "/USB_D+") (class "Default")
      (node (ref "C14") (pin "2") (pinfunction "2_2") (pintype "passive"))
      (node (ref "LPC1") (pin "37") (pinfunction "37_37") (pintype "passive"))
      (node (ref "R17") (pin "1") (pinfunction "1_1") (pintype "passive"))
      (node (ref "R20") (pin "2") (pinfunction "2_2") (pintype "passive"))
    )
    (net (code "68") (name "/USB_D-") (class "Default")
      (node (ref "C13") (pin "2") (pinfunction "2_2") (pintype "passive"))
      (node (ref "LPC1") (pin "36") (pinfunction "36_36") (pintype "passive"))
      (node (ref "R21") (pin "2") (pinfunction "2_2") (pintype "passive"))
    )
    (net (code "69") (name "/VBB") (class "Default")
      (node (ref "C12") (pin "+") (pinfunction "+_+") (pintype "passive"))
      (node (ref "C21") (pin "+") (pinfunction "+_+") (pintype "passive"))
      (node (ref "C25") (pin "+") (pinfunction "+_+") (pintype "passive"))
      (node (ref "C26") (pin "+") (pinfunction "+_+") (pintype "passive"))
      (node (ref "D3") (pin "C") (pinfunction "C_C") (pintype "passive"))
      (node (ref "M1") (pin "8") (pinfunction "VMOT_8") (pintype "power_in"))
      (node (ref "M2") (pin "8") (pinfunction "VMOT_8") (pintype "power_in"))
      (node (ref "M3") (pin "8") (pinfunction "VMOT_8") (pintype "power_in"))
      (node (ref "M4") (pin "8") (pinfunction "VMOT_8") (pintype "power_in"))
      (node (ref "Q5") (pin "S") (pinfunction "S_S") (pintype "passive"))
      (node (ref "R54") (pin "2") (pinfunction "2_2") (pintype "passive"))
    )
    (net (code "70") (name "/VBB_IN") (class "Default")
      (node (ref "Q5") (pin "D") (pinfunction "D_D") (pintype "passive"))
      (node (ref "X7") (pin "2") (pinfunction "SK_2") (pintype "passive"))
    )
    (net (code "71") (name "/X_MAX") (class "Default")
      (node (ref "C16") (pin "1") (pinfunction "1_1") (pintype "passive"))
      (node (ref "LPC1") (pin "66") (pinfunction "66_66") (pintype "passive"))
      (node (ref "R25") (pin "2") (pinfunction "2_2") (pintype "passive"))
    )
    (net (code "72") (name "/X_MIN") (class "Default")
      (node (ref "C15") (pin "1") (pinfunction "1_1") (pintype "passive"))
      (node (ref "LPC1") (pin "67") (pinfunction "67_67") (pintype "passive"))
      (node (ref "R22") (pin "2") (pinfunction "2_2") (pintype "passive"))
    )
    (net (code "73") (name "/Y_MAX") (class "Default")
      (node (ref "C18") (pin "1") (pinfunction "1_1") (pintype "passive"))
      (node (ref "LPC1") (pin "64") (pinfunction "64_64") (pintype "passive"))
      (node (ref "R36") (pin "2") (pinfunction "2_2") (pintype "passive"))
    )
    (net (code "74") (name "/Y_MIN") (class "Default")
      (node (ref "C17") (pin "1") (pinfunction "1_1") (pintype "passive"))
      (node (ref "LPC1") (pin "65") (pinfunction "65_65") (pintype "passive"))
      (node (ref "R28") (pin "2") (pinfunction "2_2") (pintype "passive"))
    )
    (net (code "75") (name "/Z_MAX") (class "Default")
      (node (ref "C20") (pin "1") (pinfunction "1_1") (pintype "passive"))
      (node (ref "LPC1") (pin "62") (pinfunction "62_62") (pintype "passive"))
      (node (ref "R45") (pin "2") (pinfunction "2_2") (pintype "passive"))
    )
    (net (code "76") (name "/Z_MIN") (class "Default")
      (node (ref "C19") (pin "1") (pinfunction "1_1") (pintype "passive"))
      (node (ref "LPC1") (pin "63") (pinfunction "63_63") (pintype "passive"))
      (node (ref "R43") (pin "2") (pinfunction "2_2") (pintype "passive"))
    )
    (net (code "77") (name "3.3V") (class "Default")
      (node (ref "C7") (pin "2") (pinfunction "2_2") (pintype "passive"))
      (node (ref "C8") (pin "2") (pinfunction "2_2") (pintype "passive"))
      (node (ref "C9") (pin "A") (pinfunction "+_A") (pintype "passive"))
      (node (ref "D1") (pin "C") (pinfunction "C_C") (pintype "passive"))
      (node (ref "FB1") (pin "2") (pinfunction "P$2_2") (pintype "bidirectional"))
      (node (ref "JP11") (pin "6") (pinfunction "6_6") (pintype "passive"))
      (node (ref "JP12") (pin "1") (pinfunction "1_1") (pintype "passive"))
      (node (ref "JP13") (pin "1") (pinfunction "1_1") (pintype "passive"))
      (node (ref "JP7") (pin "1") (pinfunction "1_1") (pintype "passive"))
      (node (ref "JP9") (pin "1") (pinfunction "1_1") (pintype "passive"))
      (node (ref "L1") (pin "2") (pinfunction "2_2") (pintype "passive"))
      (node (ref "LPC1") (pin "28") (pinfunction "28_28") (pintype "passive"))
      (node (ref "MS1") (pin "2") (pinfunction "2_2") (pintype "passive"))
      (node (ref "MS2") (pin "2") (pinfunction "2_2") (pintype "passive"))
      (node (ref "MS3") (pin "2") (pinfunction "2_2") (pintype "passive"))
      (node (ref "Q2") (pin "2") (pinfunction "S_2") (pintype "passive"))
      (node (ref "R10") (pin "2") (pinfunction "2_2") (pintype "passive"))
      (node (ref "R11") (pin "2") (pinfunction "2_2") (pintype "passive"))
      (node (ref "R12") (pin "2") (pinfunction "2_2") (pintype "passive"))
      (node (ref "R30") (pin "2") (pinfunction "2_2") (pintype "passive"))
      (node (ref "R31") (pin "2") (pinfunction "2_2") (pintype "passive"))
      (node (ref "R32") (pin "2") (pinfunction "2_2") (pintype "passive"))
      (node (ref "R33") (pin "2") (pinfunction "2_2") (pintype "passive"))
      (node (ref "R38") (pin "2") (pinfunction "2_2") (pintype "passive"))
      (node (ref "R39") (pin "2") (pinfunction "2_2") (pintype "passive"))
      (node (ref "R46") (pin "2") (pinfunction "2_2") (pintype "passive"))
      (node (ref "R47") (pin "2") (pinfunction "2_2") (pintype "passive"))
      (node (ref "R48") (pin "2") (pinfunction "2_2") (pintype "passive"))
      (node (ref "R49") (pin "2") (pinfunction "2_2") (pintype "passive"))
      (node (ref "R50") (pin "2") (pinfunction "2_2") (pintype "passive"))
      (node (ref "R8") (pin "2") (pinfunction "2_2") (pintype "passive"))
      (node (ref "R9") (pin "2") (pinfunction "2_2") (pintype "passive"))
      (node (ref "SJ1") (pin "1") (pinfunction "1_1") (pintype "passive"))
      (node (ref "U1") (pin "4") (pinfunction "VCC_4") (pintype "bidirectional"))
      (node (ref "X2") (pin "1") (pinfunction "S_1") (pintype "passive"))
      (node (ref "X2") (pin "11") (pinfunction "S_11") (pintype "passive"))
      (node (ref "X2") (pin "2") (pinfunction "S_2") (pintype "passive"))
    )
    (net (code "78") (name "5V") (class "Default")
      (node (ref "JP13") (pin "3") (pinfunction "3_3") (pintype "passive"))
      (node (ref "JP7") (pin "3") (pinfunction "3_3") (pintype "passive"))
      (node (ref "LPC1") (pin "2") (pinfunction "2_2") (pintype "passive"))
      (node (ref "SJ1") (pin "3") (pinfunction "3_3") (pintype "passive"))
    )
    (net (code "79") (name "GND") (class "Default")
      (node (ref "ATX") (pin "C") (pinfunction "C_C") (pintype "passive"))
      (node (ref "C1") (pin "C") (pinfunction "-_C") (pintype "passive"))
      (node (ref "C10") (pin "-") (pinfunction "-_-") (pintype "passive"))
      (node (ref "C11") (pin "1") (pinfunction "1_1") (pintype "passive"))
      (node (ref "C12") (pin "-") (pinfunction "-_-") (pintype "passive"))
      (node (ref "C13") (pin "1") (pinfunction "1_1") (pintype "passive"))
      (node (ref "C14") (pin "1") (pinfunction "1_1") (pintype "passive"))
      (node (ref "C15") (pin "2") (pinfunction "2_2") (pintype "passive"))
      (node (ref "C16") (pin "2") (pinfunction "2_2") (pintype "passive"))
      (node (ref "C17") (pin "2") (pinfunction "2_2") (pintype "passive"))
      (node (ref "C18") (pin "2") (pinfunction "2_2") (pintype "passive"))
      (node (ref "C19") (pin "2") (pinfunction "2_2") (pintype "passive"))
      (node (ref "C2") (pin "C") (pinfunction "-_C") (pintype "passive"))
      (node (ref "C20") (pin "2") (pinfunction "2_2") (pintype "passive"))
      (node (ref "C21") (pin "-") (pinfunction "-_-") (pintype "passive"))
      (node (ref "C22") (pin "2") (pinfunction "2_2") (pintype "passive"))
      (node (ref "C23") (pin "C") (pinfunction "-_C") (pintype "passive"))
      (node (ref "C24") (pin "1") (pinfunction "1_1") (pintype "passive"))
      (node (ref "C25") (pin "-") (pinfunction "-_-") (pintype "passive"))
      (node (ref "C26") (pin "-") (pinfunction "-_-") (pintype "passive"))
      (node (ref "C3") (pin "C") (pinfunction "-_C") (pintype "passive"))
      (node (ref "C4") (pin "C") (pinfunction "-_C") (pintype "passive"))
      (node (ref "C5") (pin "C") (pinfunction "-_C") (pintype "passive"))
      (node (ref "C6") (pin "1") (pinfunction "1_1") (pintype "passive"))
      (node (ref "C7") (pin "1") (pinfunction "1_1") (pintype "passive"))
      (node (ref "C8") (pin "1") (pinfunction "1_1") (pintype "passive"))
      (node (ref "C9") (pin "C") (pinfunction "-_C") (pintype "passive"))
      (node (ref "D2") (pin "A") (pinfunction "A_A") (pintype "passive"))
      (node (ref "IC1") (pin "3") (pinfunction "GND_3") (pintype "power_in"))
      (node (ref "IC2") (pin "3") (pinfunction "P$2_3") (pintype "bidirectional"))
      (node (ref "J2") (pin "2") (pinfunction "S_2") (pintype "passive"))
      (node (ref "JP10") (pin "5") (pinfunction "5_5") (pintype "passive"))
      (node (ref "JP11") (pin "1") (pinfunction "1_1") (pintype "passive"))
      (node (ref "JP12") (pin "2") (pinfunction "2_2") (pintype "passive"))
      (node (ref "JP14") (pin "2") (pinfunction "2_2") (pintype "passive"))
      (node (ref "JP16") (pin "4") (pinfunction "4_4") (pintype "passive"))
      (node (ref "JP5") (pin "1") (pinfunction "1_1") (pintype "passive"))
      (node (ref "JP7") (pin "2") (pinfunction "2_2") (pintype "passive"))
      (node (ref "JP8") (pin "5") (pinfunction "5_5") (pintype "passive"))
      (node (ref "JP9") (pin "2") (pinfunction "2_2") (pintype "passive"))
      (node (ref "LED1") (pin "C") (pinfunction "C_C") (pintype "passive"))
      (node (ref "LED2") (pin "C") (pinfunction "C_C") (pintype "passive"))
      (node (ref "LED3") (pin "C") (pinfunction "C_C") (pintype "passive"))
      (node (ref "LED4") (pin "C") (pinfunction "C_C") (pintype "passive"))
      (node (ref "LEDS") (pin "2") (pinfunction "2_2") (pintype "passive"))
      (node (ref "LEDS") (pin "4") (pinfunction "4_4") (pintype "passive"))
      (node (ref "LEDS") (pin "6") (pinfunction "6_6") (pintype "passive"))
      (node (ref "LEDS") (pin "8") (pinfunction "8_8") (pintype "passive"))
      (node (ref "LPC1") (pin "1") (pinfunction "1_1") (pintype "passive"))
      (node (ref "LPC1") (pin "54") (pinfunction "54_54") (pintype "passive"))
      (node (ref "M1") (pin "1") (pinfunction "GND_1") (pintype "power_in"))
      (node (ref "M1") (pin "7") (pinfunction "GND_7") (pintype "power_in"))
      (node (ref "M2") (pin "1") (pinfunction "GND_1") (pintype "power_in"))
      (node (ref "M2") (pin "7") (pinfunction "GND_7") (pintype "power_in"))
      (node (ref "M3") (pin "1") (pinfunction "GND_1") (pintype "power_in"))
      (node (ref "M3") (pin "7") (pinfunction "GND_7") (pintype "power_in"))
      (node (ref "M4") (pin "1") (pinfunction "GND_1") (pintype "power_in"))
      (node (ref "M4") (pin "7") (pinfunction "GND_7") (pintype "power_in"))
      (node (ref "PS_ON") (pin "2") (pinfunction "2_2") (pintype "passive"))
      (node (ref "Q1") (pin "3") (pinfunction "S_3") (pintype "passive"))
      (node (ref "Q3") (pin "S") (pinfunction "S_S") (pintype "passive"))
      (node (ref "Q4") (pin "3") (pinfunction "S_3") (pintype "passive"))
      (node (ref "R15") (pin "1") (pinfunction "1_1") (pintype "passive"))
      (node (ref "R16") (pin "1") (pinfunction "1_1") (pintype "passive"))
      (node (ref "R23") (pin "2") (pinfunction "2_2") (pintype "passive"))
      (node (ref "R5") (pin "1") (pinfunction "1_1") (pintype "passive"))
      (node (ref "R53") (pin "2") (pinfunction "2_2") (pintype "passive"))
      (node (ref "R55") (pin "2") (pinfunction "2_2") (pintype "passive"))
      (node (ref "R7") (pin "2") (pinfunction "2_2") (pintype "passive"))
      (node (ref "RESET") (pin "3") (pinfunction "3_3") (pintype "passive"))
      (node (ref "RESET") (pin "4") (pinfunction "4_4") (pintype "passive"))
      (node (ref "RJ1") (pin "G+") (pinfunction "G+_G+") (pintype "bidirectional"))
      (node (ref "RJ1") (pin "G-") (pinfunction "G-_G-") (pintype "bidirectional"))
      (node (ref "RJ1") (pin "GND") (pinfunction "GND_GND") (pintype "bidirectional"))
      (node (ref "RJ1") (pin "SHIELD0") (pinfunction "SHIELD0_SHIELD0") (pintype "bidirectional"))
      (node (ref "RJ1") (pin "SHIELD1") (pinfunction "SHIELD1_SHIELD1") (pintype "bidirectional"))
      (node (ref "RJ1") (pin "Y+") (pinfunction "Y+_Y+") (pintype "bidirectional"))
      (node (ref "RJ1") (pin "Y-") (pinfunction "Y-_Y-") (pintype "bidirectional"))
      (node (ref "S1") (pin "3") (pinfunction "3_3") (pintype "passive"))
      (node (ref "S1") (pin "4") (pinfunction "4_4") (pintype "passive"))
      (node (ref "S2") (pin "3") (pinfunction "3_3") (pintype "passive"))
      (node (ref "S2") (pin "4") (pinfunction "4_4") (pintype "passive"))
      (node (ref "THERM.") (pin "1") (pinfunction "1_1") (pintype "passive"))
      (node (ref "THERM.") (pin "3") (pinfunction "3_3") (pintype "passive"))
      (node (ref "THERM.") (pin "5") (pinfunction "5_5") (pintype "passive"))
      (node (ref "THERM.") (pin "7") (pinfunction "7_7") (pintype "passive"))
      (node (ref "U1") (pin "6") (pinfunction "GND_6") (pintype "bidirectional"))
      (node (ref "U1") (pin "CD1") (pinfunction "SHIELD_CD1") (pintype "bidirectional"))
      (node (ref "U1") (pin "CD2") (pinfunction "SHIELD_CD2") (pintype "bidirectional"))
      (node (ref "U1") (pin "GND1") (pinfunction "SHIELD_GND1") (pintype "bidirectional"))
      (node (ref "U1") (pin "GND3") (pinfunction "SHIELD_GND3") (pintype "bidirectional"))
      (node (ref "USB") (pin "C") (pinfunction "C_C") (pintype "passive"))
      (node (ref "VBB") (pin "C") (pinfunction "C_C") (pintype "passive"))
      (node (ref "X1") (pin "2") (pinfunction "SK_2") (pintype "passive"))
      (node (ref "X2") (pin "13") (pinfunction "S_13") (pintype "passive"))
      (node (ref "X2") (pin "15") (pinfunction "S_15") (pintype "passive"))
      (node (ref "X2") (pin "16") (pinfunction "S_16") (pintype "passive"))
      (node (ref "X2") (pin "17") (pinfunction "S_17") (pintype "passive"))
      (node (ref "X2") (pin "3") (pinfunction "S_3") (pintype "passive"))
      (node (ref "X2") (pin "5") (pinfunction "S_5") (pintype "passive"))
      (node (ref "X2") (pin "7") (pinfunction "S_7") (pintype "passive"))
      (node (ref "X4") (pin "2") (pinfunction "SK_2") (pintype "passive"))
      (node (ref "X6") (pin "GND") (pinfunction "GND_GND") (pintype "bidirectional"))
      (node (ref "X7") (pin "1") (pinfunction "SK_1") (pintype "passive"))
      (node (ref "XMAX") (pin "2") (pinfunction "2_2") (pintype "passive"))
      (node (ref "XMIN") (pin "2") (pinfunction "2_2") (pintype "passive"))
      (node (ref "YMAX") (pin "2") (pinfunction "2_2") (pintype "passive"))
      (node (ref "YMIN") (pin "2") (pinfunction "2_2") (pintype "passive"))
      (node (ref "ZMAX") (pin "2") (pinfunction "2_2") (pintype "passive"))
      (node (ref "ZMIN") (pin "2") (pinfunction "2_2") (pintype "passive"))
    )
    (net (code "80") (name "Net-(ATX-PadA)") (class "Default")
      (node (ref "ATX") (pin "A") (pinfunction "A_A") (pintype "passive"))
      (node (ref "R3") (pin "1") (pinfunction "1_1") (pintype "passive"))
    )
    (net (code "81") (name "Net-(BIG-PadA)") (class "Default")
      (node (ref "BIG") (pin "A") (pinfunction "A_A") (pintype "passive"))
      (node (ref "R13") (pin "2") (pinfunction "2_2") (pintype "passive"))
    )
    (net (code "82") (name "Net-(D3-PadA)") (class "Default")
      (node (ref "D3") (pin "A") (pinfunction "A_A") (pintype "passive"))
      (node (ref "Q5") (pin "G") (pinfunction "G_G") (pintype "passive"))
      (node (ref "R55") (pin "1") (pinfunction "1_1") (pintype "passive"))
    )
    (net (code "83") (name "Net-(FAN-PadA)") (class "Default")
      (node (ref "FAN") (pin "A") (pinfunction "A_A") (pintype "passive"))
      (node (ref "R51") (pin "2") (pinfunction "2_2") (pintype "passive"))
    )
    (net (code "84") (name "Net-(FB1-P$1)") (class "Default")
      (node (ref "C24") (pin "2") (pinfunction "2_2") (pintype "passive"))
      (node (ref "FB1") (pin "1") (pinfunction "P$1_1") (pintype "bidirectional"))
      (node (ref "RJ1") (pin "P4") (pinfunction "P4_P4") (pintype "bidirectional"))
      (node (ref "RJ1") (pin "P5") (pinfunction "P5_P5") (pintype "bidirectional"))
    )
    (net (code "85") (name "Net-(IC1A-I)") (class "Default")
      (node (ref "IC1") (pin "2") (pinfunction "I_2") (pintype "input"))
      (node (ref "X2") (pin "8") (pinfunction "S_8") (pintype "passive"))
    )
    (net (code "86") (name "Net-(IC1A-O)") (class "Default")
      (node (ref "IC1") (pin "4") (pinfunction "O_4") (pintype "open_collector"))
      (node (ref "R1") (pin "2") (pinfunction "2_2") (pintype "passive"))
    )
    (net (code "87") (name "Net-(IC1B-VCC)") (class "Default")
      (node (ref "C6") (pin "2") (pinfunction "2_2") (pintype "passive"))
      (node (ref "IC1") (pin "5") (pinfunction "VCC_5") (pintype "power_in"))
      (node (ref "R3") (pin "2") (pinfunction "2_2") (pintype "passive"))
      (node (ref "X2") (pin "9") (pinfunction "S_9") (pintype "passive"))
    )
    (net (code "88") (name "Net-(IC2A-P$2)") (class "Default")
      (node (ref "IC2") (pin "7") (pinfunction "P$2_7") (pintype "bidirectional"))
      (node (ref "R14") (pin "1") (pinfunction "1_1") (pintype "passive"))
    )
    (net (code "89") (name "Net-(IC2B-P$1)") (class "Default")
      (node (ref "IC2") (pin "4") (pinfunction "P$1_4") (pintype "bidirectional"))
      (node (ref "R15") (pin "2") (pinfunction "2_2") (pintype "passive"))
    )
    (net (code "90") (name "Net-(J1A-S)") (class "Default")
      (node (ref "J1") (pin "1") (pinfunction "S_1") (pintype "passive"))
      (node (ref "M1") (pin "3") (pinfunction "A2_3") (pintype "output"))
    )
    (net (code "91") (name "Net-(J1B-S)") (class "Default")
      (node (ref "J1") (pin "2") (pinfunction "S_2") (pintype "passive"))
      (node (ref "M1") (pin "4") (pinfunction "A1_4") (pintype "output"))
    )
    (net (code "92") (name "Net-(J1C-S)") (class "Default")
      (node (ref "J1") (pin "3") (pinfunction "S_3") (pintype "passive"))
      (node (ref "M1") (pin "5") (pinfunction "B1_5") (pintype "output"))
    )
    (net (code "93") (name "Net-(J1D-S)") (class "Default")
      (node (ref "J1") (pin "4") (pinfunction "S_4") (pintype "passive"))
      (node (ref "M1") (pin "6") (pinfunction "B2_6") (pintype "output"))
    )
    (net (code "94") (name "Net-(J3A-S)") (class "Default")
      (node (ref "J3") (pin "1") (pinfunction "S_1") (pintype "passive"))
      (node (ref "M2") (pin "3") (pinfunction "A2_3") (pintype "output"))
    )
    (net (code "95") (name "Net-(J3B-S)") (class "Default")
      (node (ref "J3") (pin "2") (pinfunction "S_2") (pintype "passive"))
      (node (ref "M2") (pin "4") (pinfunction "A1_4") (pintype "output"))
    )
    (net (code "96") (name "Net-(J3C-S)") (class "Default")
      (node (ref "J3") (pin "3") (pinfunction "S_3") (pintype "passive"))
      (node (ref "M2") (pin "5") (pinfunction "B1_5") (pintype "output"))
    )
    (net (code "97") (name "Net-(J3D-S)") (class "Default")
      (node (ref "J3") (pin "4") (pinfunction "S_4") (pintype "passive"))
      (node (ref "M2") (pin "6") (pinfunction "B2_6") (pintype "output"))
    )
    (net (code "98") (name "Net-(J4A-S)") (class "Default")
      (node (ref "FAN") (pin "C") (pinfunction "C_C") (pintype "passive"))
      (node (ref "J4") (pin "1") (pinfunction "S_1") (pintype "passive"))
      (node (ref "Q4") (pin "4") (pinfunction "D_4") (pintype "passive"))
    )
    (net (code "99") (name "Net-(J5A-S)") (class "Default")
      (node (ref "J5") (pin "1") (pinfunction "S_1") (pintype "passive"))
      (node (ref "M3") (pin "3") (pinfunction "A2_3") (pintype "output"))
    )
    (net (code "100") (name "Net-(J5B-S)") (class "Default")
      (node (ref "J5") (pin "2") (pinfunction "S_2") (pintype "passive"))
      (node (ref "M3") (pin "4") (pinfunction "A1_4") (pintype "output"))
    )
    (net (code "101") (name "Net-(J5C-S)") (class "Default")
      (node (ref "J5") (pin "3") (pinfunction "S_3") (pintype "passive"))
      (node (ref "M3") (pin "5") (pinfunction "B1_5") (pintype "output"))
    )
    (net (code "102") (name "Net-(J5D-S)") (class "Default")
      (node (ref "J5") (pin "4") (pinfunction "S_4") (pintype "passive"))
      (node (ref "M3") (pin "6") (pinfunction "B2_6") (pintype "output"))
    )
    (net (code "103") (name "Net-(J6A-S)") (class "Default")
      (node (ref "J6") (pin "1") (pinfunction "S_1") (pintype "passive"))
      (node (ref "M4") (pin "3") (pinfunction "A2_3") (pintype "output"))
    )
    (net (code "104") (name "Net-(J6B-S)") (class "Default")
      (node (ref "J6") (pin "2") (pinfunction "S_2") (pintype "passive"))
      (node (ref "M4") (pin "4") (pinfunction "A1_4") (pintype "output"))
    )
    (net (code "105") (name "Net-(J6C-S)") (class "Default")
      (node (ref "J6") (pin "3") (pinfunction "S_3") (pintype "passive"))
      (node (ref "M4") (pin "5") (pinfunction "B1_5") (pintype "output"))
    )
    (net (code "106") (name "Net-(J6D-S)") (class "Default")
      (node (ref "J6") (pin "4") (pinfunction "S_4") (pintype "passive"))
      (node (ref "M4") (pin "6") (pinfunction "B2_6") (pintype "output"))
    )
    (net (code "107") (name "Net-(JP5-Pad2)") (class "Default")
      (node (ref "JP5") (pin "2") (pinfunction "2_2") (pintype "passive"))
      (node (ref "R4") (pin "1") (pinfunction "1_1") (pintype "passive"))
      (node (ref "R5") (pin "2") (pinfunction "2_2") (pintype "passive"))
    )
    (net (code "108") (name "Net-(JP7-Pad4)") (class "Default")
      (node (ref "JP7") (pin "4") (pinfunction "4_4") (pintype "passive"))
      (node (ref "LPC1") (pin "3") (pinfunction "3_3") (pintype "passive"))
    )
    (net (code "109") (name "Net-(JP13-Pad2)") (class "Default")
      (node (ref "JP13") (pin "2") (pinfunction "2_2") (pintype "passive"))
      (node (ref "R19") (pin "2") (pinfunction "2_2") (pintype "passive"))
      (node (ref "R24") (pin "2") (pinfunction "2_2") (pintype "passive"))
      (node (ref "R27") (pin "2") (pinfunction "2_2") (pintype "passive"))
      (node (ref "R34") (pin "2") (pinfunction "2_2") (pintype "passive"))
      (node (ref "R40") (pin "2") (pinfunction "2_2") (pintype "passive"))
      (node (ref "R44") (pin "2") (pinfunction "2_2") (pintype "passive"))
      (node (ref "XMAX") (pin "3") (pinfunction "3_3") (pintype "passive"))
      (node (ref "XMIN") (pin "3") (pinfunction "3_3") (pintype "passive"))
      (node (ref "YMAX") (pin "3") (pinfunction "3_3") (pintype "passive"))
      (node (ref "YMIN") (pin "3") (pinfunction "3_3") (pintype "passive"))
      (node (ref "ZMAX") (pin "3") (pinfunction "3_3") (pintype "passive"))
      (node (ref "ZMIN") (pin "3") (pinfunction "3_3") (pintype "passive"))
    )
    (net (code "110") (name "Net-(JP15-Pad1)") (class "Default")
      (node (ref "JP15") (pin "1") (pinfunction "1_1") (pintype "passive"))
      (node (ref "PLAY") (pin "C") (pinfunction "C_C") (pintype "passive"))
      (node (ref "R33") (pin "1") (pinfunction "1_1") (pintype "passive"))
    )
    (net (code "111") (name "Net-(LED1-PadA)") (class "Default")
      (node (ref "LED1") (pin "A") (pinfunction "A_A") (pintype "passive"))
      (node (ref "R26") (pin "1") (pinfunction "1_1") (pintype "passive"))
    )
    (net (code "112") (name "Net-(LED2-PadA)") (class "Default")
      (node (ref "LED2") (pin "A") (pinfunction "A_A") (pintype "passive"))
      (node (ref "R29") (pin "1") (pinfunction "1_1") (pintype "passive"))
    )
    (net (code "113") (name "Net-(LED3-PadA)") (class "Default")
      (node (ref "LED3") (pin "A") (pinfunction "A_A") (pintype "passive"))
      (node (ref "R35") (pin "1") (pinfunction "1_1") (pintype "passive"))
    )
    (net (code "114") (name "Net-(LED4-PadA)") (class "Default")
      (node (ref "LED4") (pin "A") (pinfunction "A_A") (pintype "passive"))
      (node (ref "R37") (pin "1") (pinfunction "1_1") (pintype "passive"))
    )
    (net (code "115") (name "Net-(M1-{slash}RESET)") (class "Default")
      (node (ref "M1") (pin "13") (pinfunction "/RESET_13") (pintype "input"))
      (node (ref "R12") (pin "1") (pinfunction "1_1") (pintype "passive"))
    )
    (net (code "116") (name "Net-(M1-{slash}SLEEP)") (class "Default")
      (node (ref "M1") (pin "14") (pinfunction "/SLEEP_14") (pintype "input"))
      (node (ref "R11") (pin "1") (pinfunction "1_1") (pintype "passive"))
    )
    (net (code "117") (name "Net-(M2-{slash}RESET)") (class "Default")
      (node (ref "M2") (pin "13") (pinfunction "/RESET_13") (pintype "input"))
      (node (ref "R39") (pin "1") (pinfunction "1_1") (pintype "passive"))
    )
    (net (code "118") (name "Net-(M2-{slash}SLEEP)") (class "Default")
      (node (ref "M2") (pin "14") (pinfunction "/SLEEP_14") (pintype "input"))
      (node (ref "R38") (pin "1") (pinfunction "1_1") (pintype "passive"))
    )
    (net (code "119") (name "Net-(M3-{slash}RESET)") (class "Default")
      (node (ref "M3") (pin "13") (pinfunction "/RESET_13") (pintype "input"))
      (node (ref "R48") (pin "1") (pinfunction "1_1") (pintype "passive"))
    )
    (net (code "120") (name "Net-(M3-{slash}SLEEP)") (class "Default")
      (node (ref "M3") (pin "14") (pinfunction "/SLEEP_14") (pintype "input"))
      (node (ref "R47") (pin "1") (pinfunction "1_1") (pintype "passive"))
    )
    (net (code "121") (name "Net-(M4-{slash}RESET)") (class "Default")
      (node (ref "M4") (pin "13") (pinfunction "/RESET_13") (pintype "input"))
      (node (ref "R50") (pin "1") (pinfunction "1_1") (pintype "passive"))
    )
    (net (code "122") (name "Net-(M4-{slash}SLEEP)") (class "Default")
      (node (ref "M4") (pin "14") (pinfunction "/SLEEP_14") (pintype "input"))
      (node (ref "R49") (pin "1") (pinfunction "1_1") (pintype "passive"))
    )
    (net (code "123") (name "Net-(Q1-D)") (class "Default")
      (node (ref "Q1") (pin "4") (pinfunction "D_4") (pintype "passive"))
      (node (ref "SMALL") (pin "C") (pinfunction "C_C") (pintype "passive"))
      (node (ref "X3") (pin "2") (pinfunction "SK_2") (pintype "passive"))
    )
    (net (code "124") (name "Net-(Q1-G)") (class "Default")
      (node (ref "Q1") (pin "1") (pinfunction "G_1") (pintype "passive"))
      (node (ref "R6") (pin "1") (pinfunction "1_1") (pintype "passive"))
    )
    (net (code "125") (name "Net-(Q2-D)") (class "Default")
      (node (ref "Q2") (pin "3") (pinfunction "D_3") (pintype "passive"))
      (node (ref "R17") (pin "2") (pinfunction "2_2") (pintype "passive"))
    )
    (net (code "126") (name "Net-(Q4-G)") (class "Default")
      (node (ref "Q4") (pin "1") (pinfunction "G_1") (pintype "passive"))
      (node (ref "R52") (pin "1") (pinfunction "1_1") (pintype "passive"))
    )
    (net (code "127") (name "Net-(R2-Pad2)") (class "Default")
      (node (ref "R2") (pin "2") (pinfunction "2_2") (pintype "passive"))
      (node (ref "SMALL") (pin "A") (pinfunction "A_A") (pintype "passive"))
    )
    (net (code "128") (name "Net-(R18-Pad1)") (class "Default")
      (node (ref "R18") (pin "1") (pinfunction "1_1") (pintype "passive"))
      (node (ref "USB") (pin "A") (pinfunction "A_A") (pintype "passive"))
    )
    (net (code "129") (name "Net-(R19-Pad1)") (class "Default")
      (node (ref "R19") (pin "1") (pinfunction "1_1") (pintype "passive"))
      (node (ref "R22") (pin "1") (pinfunction "1_1") (pintype "passive"))
      (node (ref "XMIN") (pin "1") (pinfunction "1_1") (pintype "passive"))
    )
    (net (code "130") (name "Net-(R20-Pad1)") (class "Default")
      (node (ref "R20") (pin "1") (pinfunction "1_1") (pintype "passive"))
      (node (ref "X6") (pin "D+") (pinfunction "D+_D+") (pintype "bidirectional"))
    )
    (net (code "131") (name "Net-(R21-Pad1)") (class "Default")
      (node (ref "R21") (pin "1") (pinfunction "1_1") (pintype "passive"))
      (node (ref "X6") (pin "D-") (pinfunction "D-_D-") (pintype "bidirectional"))
    )
    (net (code "132") (name "Net-(R24-Pad1)") (class "Default")
      (node (ref "R24") (pin "1") (pinfunction "1_1") (pintype "passive"))
      (node (ref "R25") (pin "1") (pinfunction "1_1") (pintype "passive"))
      (node (ref "XMAX") (pin "1") (pinfunction "1_1") (pintype "passive"))
    )
    (net (code "133") (name "Net-(R27-Pad1)") (class "Default")
      (node (ref "R27") (pin "1") (pinfunction "1_1") (pintype "passive"))
      (node (ref "R28") (pin "1") (pinfunction "1_1") (pintype "passive"))
      (node (ref "YMIN") (pin "1") (pinfunction "1_1") (pintype "passive"))
    )
    (net (code "134") (name "Net-(R34-Pad1)") (class "Default")
      (node (ref "R34") (pin "1") (pinfunction "1_1") (pintype "passive"))
      (node (ref "R36") (pin "1") (pinfunction "1_1") (pintype "passive"))
      (node (ref "YMAX") (pin "1") (pinfunction "1_1") (pintype "passive"))
    )
    (net (code "135") (name "Net-(R40-Pad1)") (class "Default")
      (node (ref "R40") (pin "1") (pinfunction "1_1") (pintype "passive"))
      (node (ref "R43") (pin "1") (pinfunction "1_1") (pintype "passive"))
      (node (ref "ZMIN") (pin "1") (pinfunction "1_1") (pintype "passive"))
    )
    (net (code "136") (name "Net-(R41-Pad2)") (class "Default")
      (node (ref "R41") (pin "2") (pinfunction "2_2") (pintype "passive"))
      (node (ref "R42") (pin "2") (pinfunction "2_2") (pintype "passive"))
      (node (ref "SJ1") (pin "2") (pinfunction "2_2") (pintype "passive"))
    )
    (net (code "137") (name "Net-(R44-Pad1)") (class "Default")
      (node (ref "R44") (pin "1") (pinfunction "1_1") (pintype "passive"))
      (node (ref "R45") (pin "1") (pinfunction "1_1") (pintype "passive"))
      (node (ref "ZMAX") (pin "1") (pinfunction "1_1") (pintype "passive"))
    )
    (net (code "138") (name "Net-(R54-Pad1)") (class "Default")
      (node (ref "R54") (pin "1") (pinfunction "1_1") (pintype "passive"))
      (node (ref "VBB") (pin "A") (pinfunction "A_A") (pintype "passive"))
    )
    (net (code "139") (name "Net-(X2F-S)") (class "Default")
      (node (ref "PS_ON") (pin "1") (pinfunction "1_1") (pintype "passive"))
      (node (ref "X2") (pin "14") (pinfunction "S_14") (pintype "passive"))
    )
    (net (code "140") (name "Net-(X5B-SK)") (class "Default")
      (node (ref "BIG") (pin "C") (pinfunction "C_C") (pintype "passive"))
      (node (ref "Q3") (pin "D") (pinfunction "D_D") (pintype "passive"))
      (node (ref "X5") (pin "2") (pinfunction "SK_2") (pintype "passive"))
    )
    (net (code "141") (name "VUSB") (class "Default")
      (node (ref "R18") (pin "2") (pinfunction "2_2") (pintype "passive"))
      (node (ref "X6") (pin "VBUS") (pinfunction "VBUS_VBUS") (pintype "bidirectional"))
    )
    (net (code "142") (name "unconnected-(H1-MOUNT-PadB3,2)") (class "Default")
      (node (ref "H1") (pin "B3,2") (pinfunction "MOUNT_B3,2") (pintype "passive"))
    )
    (net (code "143") (name "unconnected-(H2-MOUNT-PadB3,2)") (class "Default")
      (node (ref "H2") (pin "B3,2") (pinfunction "MOUNT_B3,2") (pintype "passive"))
    )
    (net (code "144") (name "unconnected-(H3-MOUNT-PadB3,2)") (class "Default")
      (node (ref "H3") (pin "B3,2") (pinfunction "MOUNT_B3,2") (pintype "passive"))
    )
    (net (code "145") (name "unconnected-(H4-MOUNT-PadB3,2)") (class "Default")
      (node (ref "H4") (pin "B3,2") (pinfunction "MOUNT_B3,2") (pintype "passive"))
    )
    (net (code "146") (name "unconnected-(IC2B-P$2-Pad5)") (class "Default")
      (node (ref "IC2") (pin "5") (pinfunction "P$2_5") (pintype "bidirectional"))
    )
    (net (code "147") (name "unconnected-(J4C-S-Pad3)") (class "Default")
      (node (ref "J4") (pin "3") (pinfunction "S_3") (pintype "passive"))
    )
    (net (code "148") (name "unconnected-(LPC1-Pad29)") (class "Default")
      (node (ref "LPC1") (pin "29") (pinfunction "29_29") (pintype "passive"))
    )
    (net (code "149") (name "unconnected-(LPC1-Pad30)") (class "Default")
      (node (ref "LPC1") (pin "30") (pinfunction "30_30") (pintype "passive"))
    )
    (net (code "150") (name "unconnected-(LPC1-Pad31)") (class "Default")
      (node (ref "LPC1") (pin "31") (pinfunction "31_31") (pintype "passive"))
    )
    (net (code "151") (name "unconnected-(M1-FAULT-Pad2)") (class "Default")
      (node (ref "M1") (pin "2") (pinfunction "FAULT_2") (pintype "output"))
    )
    (net (code "152") (name "unconnected-(M2-FAULT-Pad2)") (class "Default")
      (node (ref "M2") (pin "2") (pinfunction "FAULT_2") (pintype "output"))
    )
    (net (code "153") (name "unconnected-(M3-FAULT-Pad2)") (class "Default")
      (node (ref "M3") (pin "2") (pinfunction "FAULT_2") (pintype "output"))
    )
    (net (code "154") (name "unconnected-(M4-FAULT-Pad2)") (class "Default")
      (node (ref "M4") (pin "2") (pinfunction "FAULT_2") (pintype "output"))
    )
    (net (code "155") (name "unconnected-(RJ1-PadNC)") (class "Default")
      (node (ref "RJ1") (pin "NC") (pinfunction "NC_NC") (pintype "bidirectional"))
    )
    (net (code "156") (name "unconnected-(U1-NC-Pad1)") (class "Default")
      (node (ref "U1") (pin "1") (pinfunction "NC_1") (pintype "bidirectional"))
    )
    (net (code "157") (name "unconnected-(U1-RSV-Pad8)") (class "Default")
      (node (ref "U1") (pin "8") (pinfunction "RSV_8") (pintype "bidirectional"))
    )
  )
)
